# 4BitComputerSchematic.net
KiCad netlist of a schematic drawn in EasyEDA
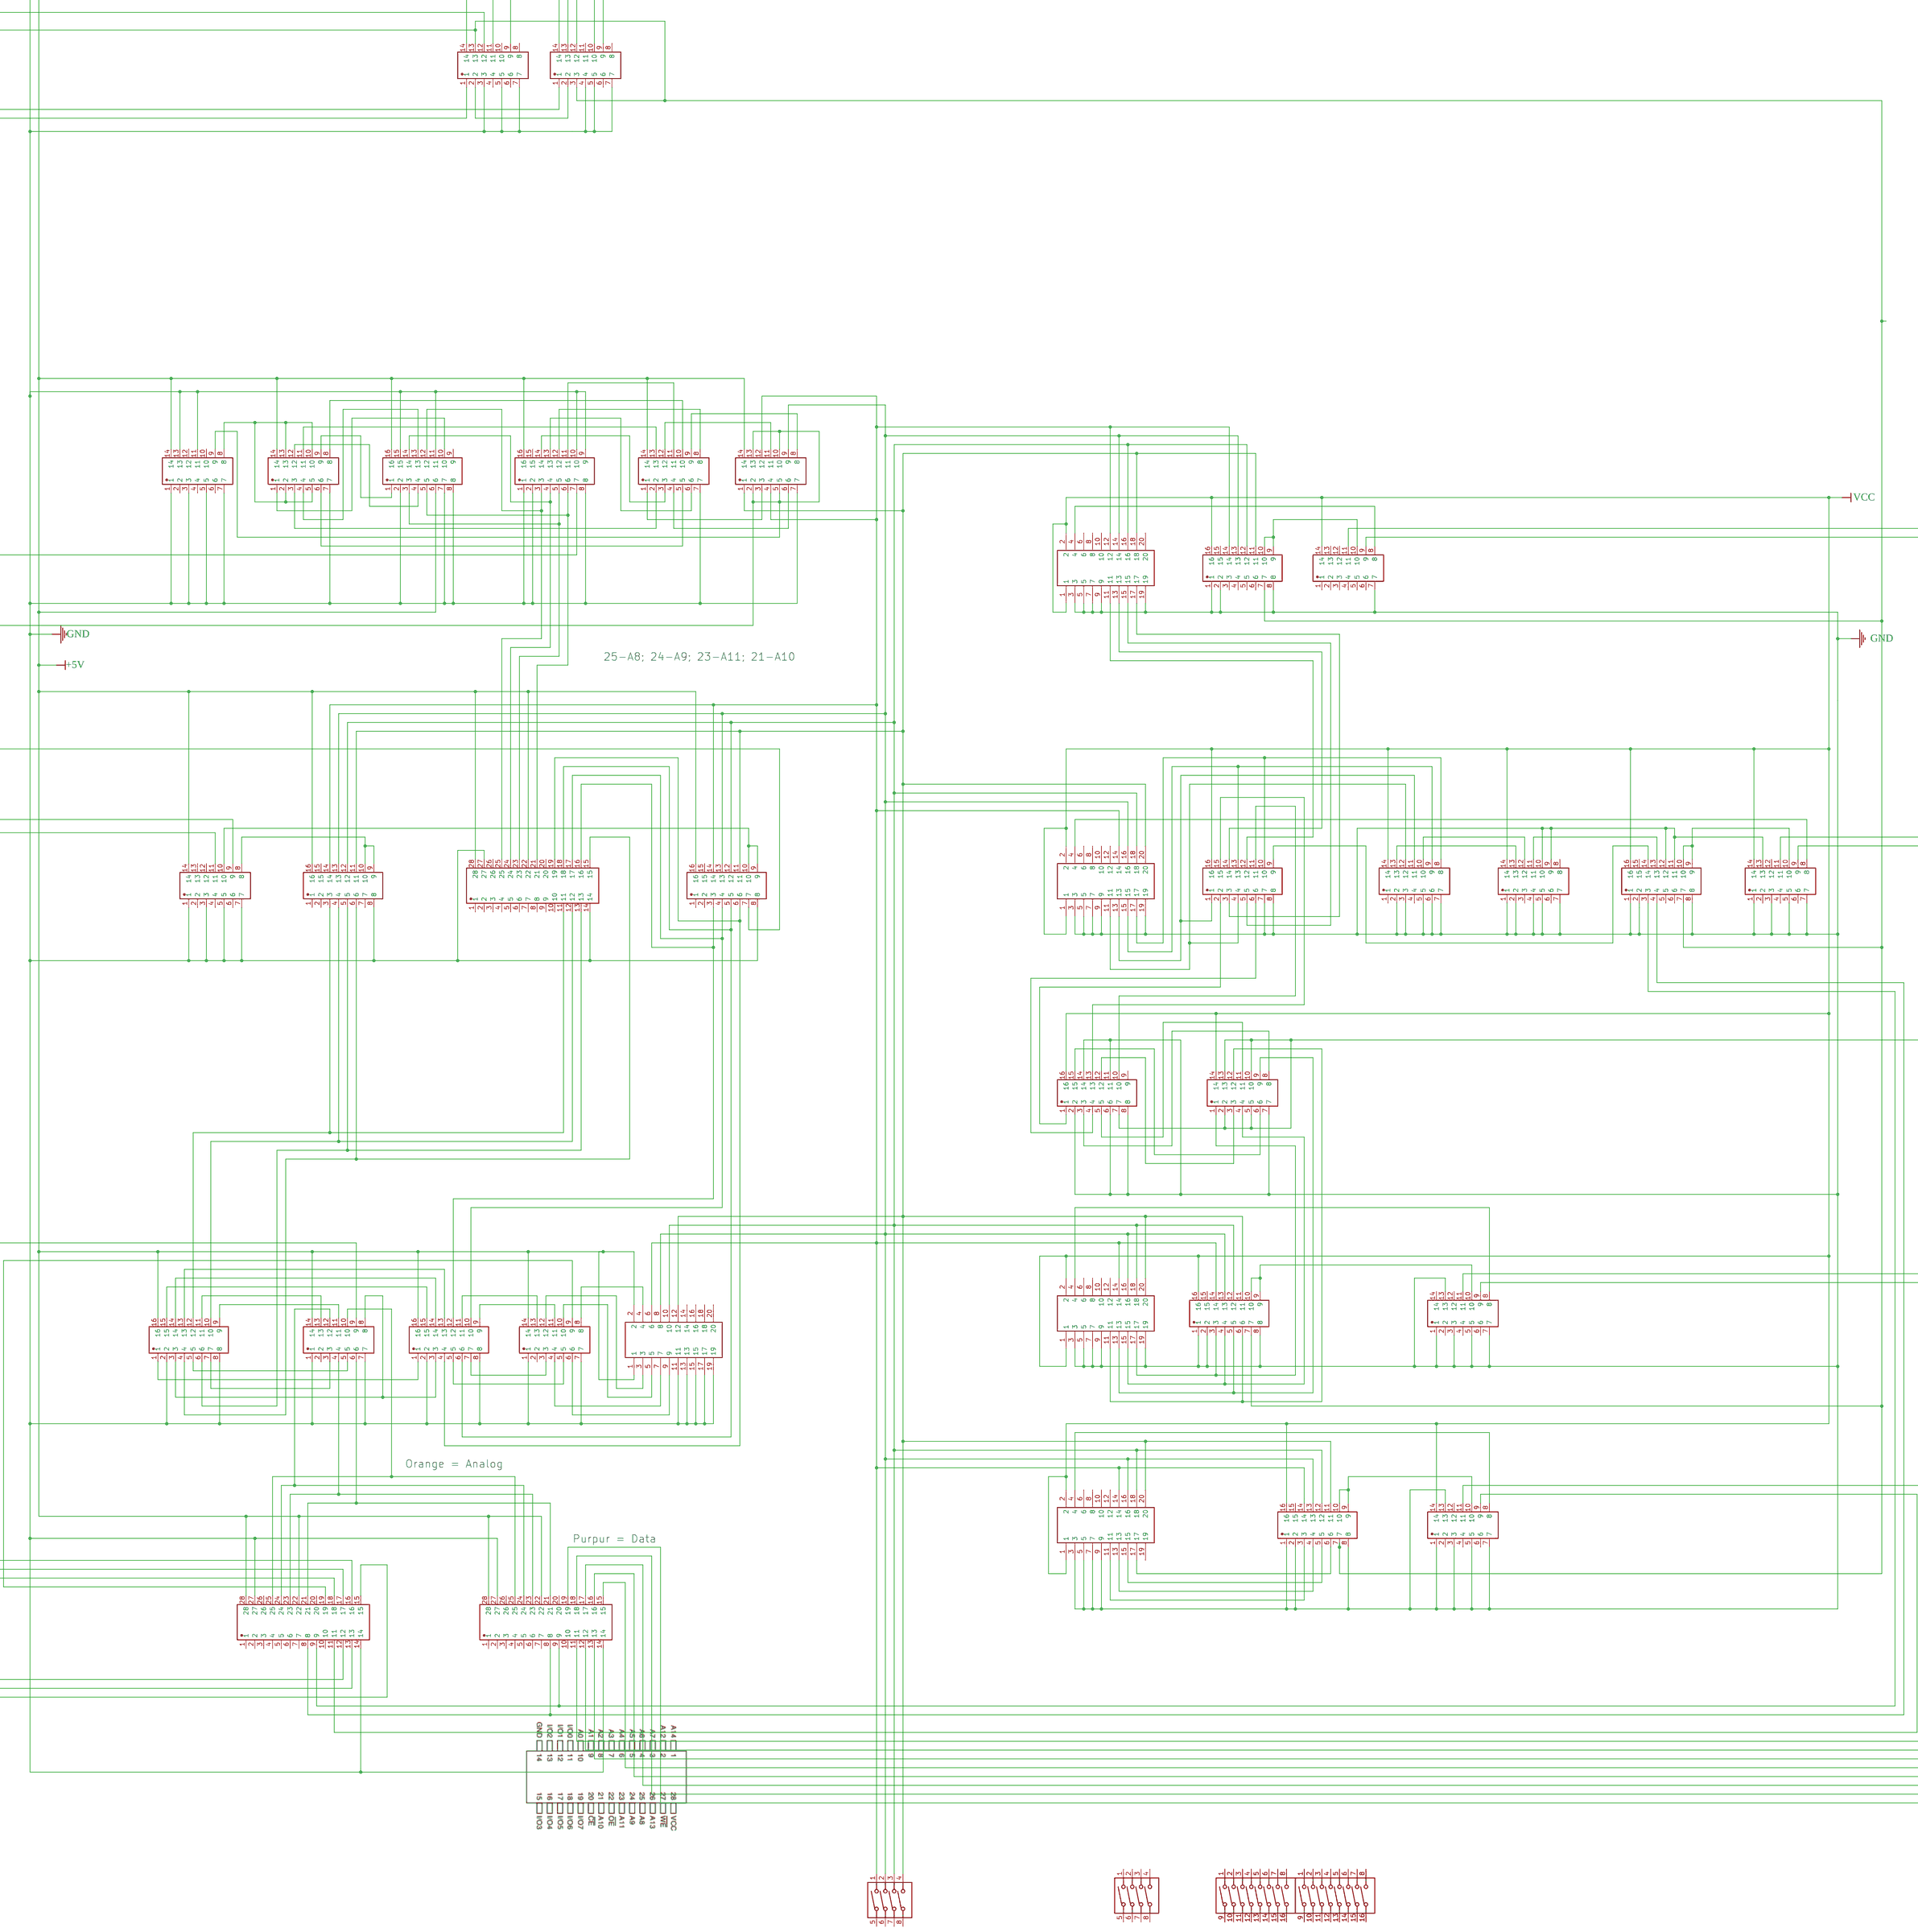
[diagram p0: schematic sheet]

(export (version "E")
  (design (tool "Eeschema 10.0.6"))
  (components
    (comp (ref "SK2")
      (value "IC seat 16P")
      (fields (field (name "Manufacturer Part") "IC-16P窄") (field (name "Manufacturer") "BOOMELE(博穆精密)"))
      (libsource (lib "") (part "IC seat 16P"))
    )
    (comp (ref "SK3")
      (value "ICS-20P")
      (fields (field (name "Manufacturer Part") "Z-ICS0S20P-NG00") (field (name "Manufacturer") "Ckmtw(灿科盟)"))
      (libsource (lib "") (part "ICS-20P"))
    )
    (comp (ref "SK4")
      (value "ICS-20P")
      (fields (field (name "Manufacturer Part") "Z-ICS0S20P-NG00") (field (name "Manufacturer") "Ckmtw(灿科盟)"))
      (libsource (lib "") (part "ICS-20P"))
    )
    (comp (ref "SK5")
      (value "ICS-20P")
      (fields (field (name "Manufacturer Part") "Z-ICS0S20P-NG00") (field (name "Manufacturer") "Ckmtw(灿科盟)"))
      (libsource (lib "") (part "ICS-20P"))
    )
    (comp (ref "SK7")
      (value "1-2199298-3")
      (fields (field (name "Manufacturer") "TE Connectivity(美国泰科)"))
      (libsource (lib "") (part "1-2199298-3"))
    )
    (comp (ref "SK8")
      (value "1-2199298-3")
      (fields (field (name "Manufacturer") "TE Connectivity(美国泰科)"))
      (libsource (lib "") (part "1-2199298-3"))
    )
    (comp (ref "SK9")
      (value "1-2199298-3")
      (fields (field (name "Manufacturer") "TE Connectivity(美国泰科)"))
      (libsource (lib "") (part "1-2199298-3"))
    )
    (comp (ref "SK10")
      (value "1-2199298-3")
      (fields (field (name "Manufacturer") "TE Connectivity(美国泰科)"))
      (libsource (lib "") (part "1-2199298-3"))
    )
    (comp (ref "SK11")
      (value "1-2199298-3")
      (fields (field (name "Manufacturer") "TE Connectivity(美国泰科)"))
      (libsource (lib "") (part "1-2199298-3"))
    )
    (comp (ref "SK12")
      (value "1-2199298-3")
      (fields (field (name "Manufacturer") "TE Connectivity(美国泰科)"))
      (libsource (lib "") (part "1-2199298-3"))
    )
    (comp (ref "SK13")
      (value "1-2199298-3")
      (fields (field (name "Manufacturer") "TE Connectivity(美国泰科)"))
      (libsource (lib "") (part "1-2199298-3"))
    )
    (comp (ref "SK14")
      (value "1-2199298-3")
      (fields (field (name "Manufacturer") "TE Connectivity(美国泰科)"))
      (libsource (lib "") (part "1-2199298-3"))
    )
    (comp (ref "SK15")
      (value "1-2199298-3")
      (fields (field (name "Manufacturer") "TE Connectivity(美国泰科)"))
      (libsource (lib "") (part "1-2199298-3"))
    )
    (comp (ref "SK16")
      (value "1-2199298-3")
      (fields (field (name "Manufacturer") "TE Connectivity(美国泰科)"))
      (libsource (lib "") (part "1-2199298-3"))
    )
    (comp (ref "SK21")
      (value "IC seat 16P")
      (fields (field (name "Manufacturer Part") "IC-16P窄") (field (name "Manufacturer") "BOOMELE(博穆精密)"))
      (libsource (lib "") (part "IC seat 16P"))
    )
    (comp (ref "SK22")
      (value "IC seat 16P")
      (fields (field (name "Manufacturer Part") "IC-16P窄") (field (name "Manufacturer") "BOOMELE(博穆精密)"))
      (libsource (lib "") (part "IC seat 16P"))
    )
    (comp (ref "SK23")
      (value "IC seat 16P")
      (fields (field (name "Manufacturer Part") "IC-16P窄") (field (name "Manufacturer") "BOOMELE(博穆精密)"))
      (libsource (lib "") (part "IC seat 16P"))
    )
    (comp (ref "SK26")
      (value "ICS-20P")
      (fields (field (name "Manufacturer Part") "Z-ICS0S20P-NG00") (field (name "Manufacturer") "Ckmtw(灿科盟)"))
      (libsource (lib "") (part "ICS-20P"))
    )
    (comp (ref "SK27")
      (value "IC seat 16P")
      (fields (field (name "Manufacturer Part") "IC-16P窄") (field (name "Manufacturer") "BOOMELE(博穆精密)"))
      (libsource (lib "") (part "IC seat 16P"))
    )
    (comp (ref "SK28")
      (value "IC seat 16P")
      (fields (field (name "Manufacturer Part") "IC-16P窄") (field (name "Manufacturer") "BOOMELE(博穆精密)"))
      (libsource (lib "") (part "IC seat 16P"))
    )
    (comp (ref "SK31")
      (value "1-2199298-3")
      (fields (field (name "Manufacturer") "TE Connectivity(美国泰科)"))
      (libsource (lib "") (part "1-2199298-3"))
    )
    (comp (ref "SK32")
      (value "1-2199298-3")
      (fields (field (name "Manufacturer") "TE Connectivity(美国泰科)"))
      (libsource (lib "") (part "1-2199298-3"))
    )
    (comp (ref "SK33")
      (value "1-2199298-3")
      (fields (field (name "Manufacturer") "TE Connectivity(美国泰科)"))
      (libsource (lib "") (part "1-2199298-3"))
    )
    (comp (ref "SK34")
      (value "1-2199298-3")
      (fields (field (name "Manufacturer") "TE Connectivity(美国泰科)"))
      (libsource (lib "") (part "1-2199298-3"))
    )
    (comp (ref "SK35")
      (value "1-2199298-3")
      (fields (field (name "Manufacturer") "TE Connectivity(美国泰科)"))
      (libsource (lib "") (part "1-2199298-3"))
    )
    (comp (ref "SK36")
      (value "1-2199298-3")
      (fields (field (name "Manufacturer") "TE Connectivity(美国泰科)"))
      (libsource (lib "") (part "1-2199298-3"))
    )
    (comp (ref "SK37")
      (value "ICS-20P")
      (fields (field (name "Manufacturer Part") "Z-ICS0S20P-NG00") (field (name "Manufacturer") "Ckmtw(灿科盟)"))
      (libsource (lib "") (part "ICS-20P"))
    )
    (comp (ref "SW1")
      (value "DSWB08LHGET")
      (fields (field (name "Manufacturer Part") "拨码开关,平拨开关,DSWB08LHGET") (field (name "Manufacturer") "YE"))
      (libsource (lib "") (part "DSWB08LHGET"))
    )
    (comp (ref "SW2")
      (value "DSWB08LHGET")
      (fields (field (name "Manufacturer Part") "拨码开关,平拨开关,DSWB08LHGET") (field (name "Manufacturer") "YE"))
      (libsource (lib "") (part "DSWB08LHGET"))
    )
    (comp (ref "SW3")
      (value "DSWB04LHGET")
      (fields (field (name "Manufacturer Part") "拨码开关,平拨开关,DSWB04LHGET") (field (name "Manufacturer") "YE"))
      (libsource (lib "") (part "DSWB04LHGET"))
    )
    (comp (ref "SW4")
      (value "DSWB04LHGET")
      (fields (field (name "Manufacturer Part") "拨码开关,平拨开关,DSWB04LHGET") (field (name "Manufacturer") "YE"))
      (libsource (lib "") (part "DSWB04LHGET"))
    )
    (comp (ref "U2")
      (value "X5621WV-2X14-C762D1196-1196")
      (fields
        (field (name "Manufacturer Part") "X5621WV-2x14-C762D1196-1196")
        (field (name "Manufacturer") "XKB Connectivity(中国星坤)")
      )
      (libsource (lib "") (part "X5621WV-2X14-C762D1196-1196"))
    )
    (comp (ref "U4")
      (value "X5621WV-2X14-C762D1196-1196")
      (fields
        (field (name "Manufacturer Part") "X5621WV-2x14-C762D1196-1196")
        (field (name "Manufacturer") "XKB Connectivity(中国星坤)")
      )
      (libsource (lib "") (part "X5621WV-2X14-C762D1196-1196"))
    )
    (comp (ref "U5")
      (value "IC-16P")
      (fields (field (name "Manufacturer") "ZHOURI(洲日)"))
      (libsource (lib "") (part "IC-16P"))
    )
    (comp (ref "U6")
      (value "IC-16P")
      (fields (field (name "Manufacturer") "ZHOURI(洲日)"))
      (libsource (lib "") (part "IC-16P"))
    )
    (comp (ref "U7")
      (value "IC-16P")
      (fields (field (name "Manufacturer") "ZHOURI(洲日)"))
      (libsource (lib "") (part "IC-16P"))
    )
    (comp (ref "U8")
      (value "IC-16P")
      (fields (field (name "Manufacturer") "ZHOURI(洲日)"))
      (libsource (lib "") (part "IC-16P"))
    )
    (comp (ref "U9")
      (value "IC-16P")
      (fields (field (name "Manufacturer") "ZHOURI(洲日)"))
      (libsource (lib "") (part "IC-16P"))
    )
    (comp (ref "U10")
      (value "IC-16P")
      (fields (field (name "Manufacturer") "ZHOURI(洲日)"))
      (libsource (lib "") (part "IC-16P"))
    )
    (comp (ref "U11")
      (value "X5621WV-2X14-C762D1196-1196")
      (fields
        (field (name "Manufacturer Part") "X5621WV-2x14-C762D1196-1196")
        (field (name "Manufacturer") "XKB Connectivity(中国星坤)")
      )
      (libsource (lib "") (part "X5621WV-2X14-C762D1196-1196"))
    )
  )
  (nets
    (net (code "1") (name "+5V") (class "Default")
      (node (ref "SK11") (pin "14") (pinfunction "14_14") (pintype "unspecified"))
      (node (ref "SK12") (pin "14") (pinfunction "14_14") (pintype "unspecified"))
      (node (ref "SK31") (pin "14") (pinfunction "14_14") (pintype "unspecified"))
      (node (ref "SK32") (pin "14") (pinfunction "14_14") (pintype "unspecified"))
      (node (ref "SK33") (pin "14") (pinfunction "14_14") (pintype "unspecified"))
      (node (ref "SK34") (pin "14") (pinfunction "14_14") (pintype "unspecified"))
      (node (ref "SK35") (pin "14") (pinfunction "14_14") (pintype "unspecified"))
      (node (ref "SK36") (pin "14") (pinfunction "14_14") (pintype "unspecified"))
      (node (ref "SK37") (pin "1") (pinfunction "1_1") (pintype "unspecified"))
      (node (ref "SK37") (pin "2") (pinfunction "2_2") (pintype "unspecified"))
      (node (ref "SK7") (pin "14") (pinfunction "14_14") (pintype "unspecified"))
      (node (ref "U10") (pin "16") (pinfunction "16_16") (pintype "unspecified"))
      (node (ref "U11") (pin "22") (pinfunction "22_22") (pintype "unspecified"))
      (node (ref "U11") (pin "28") (pinfunction "28_28") (pintype "unspecified"))
      (node (ref "U2") (pin "22") (pinfunction "22_22") (pintype "unspecified"))
      (node (ref "U2") (pin "28") (pinfunction "28_28") (pintype "unspecified"))
      (node (ref "U4") (pin "22") (pinfunction "22_22") (pintype "unspecified"))
      (node (ref "U4") (pin "28") (pinfunction "28_28") (pintype "unspecified"))
      (node (ref "U5") (pin "16") (pinfunction "16_16") (pintype "unspecified"))
      (node (ref "U5") (pin "6") (pinfunction "6_6") (pintype "unspecified"))
      (node (ref "U6") (pin "16") (pinfunction "16_16") (pintype "unspecified"))
      (node (ref "U7") (pin "16") (pinfunction "16_16") (pintype "unspecified"))
      (node (ref "U8") (pin "16") (pinfunction "16_16") (pintype "unspecified"))
      (node (ref "U9") (pin "16") (pinfunction "16_16") (pintype "unspecified"))
    )
    (net (code "2") (name "GND") (class "Default")
      (node (ref "SK10") (pin "7") (pinfunction "7_7") (pintype "unspecified"))
      (node (ref "SK11") (pin "11") (pinfunction "11_11") (pintype "unspecified"))
      (node (ref "SK11") (pin "3") (pinfunction "3_3") (pintype "unspecified"))
      (node (ref "SK11") (pin "5") (pinfunction "5_5") (pintype "unspecified"))
      (node (ref "SK11") (pin "7") (pinfunction "7_7") (pintype "unspecified"))
      (node (ref "SK11") (pin "9") (pinfunction "9_9") (pintype "unspecified"))
      (node (ref "SK12") (pin "1") (pinfunction "1_1") (pintype "unspecified"))
      (node (ref "SK12") (pin "3") (pinfunction "3_3") (pintype "unspecified"))
      (node (ref "SK12") (pin "5") (pinfunction "5_5") (pintype "unspecified"))
      (node (ref "SK12") (pin "7") (pinfunction "7_7") (pintype "unspecified"))
      (node (ref "SK13") (pin "1") (pinfunction "1_1") (pintype "unspecified"))
      (node (ref "SK13") (pin "13") (pinfunction "13_13") (pintype "unspecified"))
      (node (ref "SK13") (pin "3") (pinfunction "3_3") (pintype "unspecified"))
      (node (ref "SK13") (pin "5") (pinfunction "5_5") (pintype "unspecified"))
      (node (ref "SK13") (pin "7") (pinfunction "7_7") (pintype "unspecified"))
      (node (ref "SK14") (pin "1") (pinfunction "1_1") (pintype "unspecified"))
      (node (ref "SK14") (pin "13") (pinfunction "13_13") (pintype "unspecified"))
      (node (ref "SK14") (pin "3") (pinfunction "3_3") (pintype "unspecified"))
      (node (ref "SK14") (pin "5") (pinfunction "5_5") (pintype "unspecified"))
      (node (ref "SK14") (pin "7") (pinfunction "7_7") (pintype "unspecified"))
      (node (ref "SK15") (pin "7") (pinfunction "7_7") (pintype "unspecified"))
      (node (ref "SK16") (pin "1") (pinfunction "1_1") (pintype "unspecified"))
      (node (ref "SK16") (pin "10") (pinfunction "10_10") (pintype "unspecified"))
      (node (ref "SK16") (pin "2") (pinfunction "2_2") (pintype "unspecified"))
      (node (ref "SK16") (pin "4") (pinfunction "4_4") (pintype "unspecified"))
      (node (ref "SK16") (pin "5") (pinfunction "5_5") (pintype "unspecified"))
      (node (ref "SK16") (pin "7") (pinfunction "7_7") (pintype "unspecified"))
      (node (ref "SK16") (pin "9") (pinfunction "9_9") (pintype "unspecified"))
      (node (ref "SK2") (pin "1") (pinfunction "1_1") (pintype "unspecified"))
      (node (ref "SK2") (pin "2") (pinfunction "2_2") (pintype "unspecified"))
      (node (ref "SK2") (pin "8") (pinfunction "8_8") (pintype "unspecified"))
      (node (ref "SK21") (pin "7") (pinfunction "7_7") (pintype "unspecified"))
      (node (ref "SK21") (pin "8") (pinfunction "8_8") (pintype "unspecified"))
      (node (ref "SK22") (pin "1") (pinfunction "1_1") (pintype "unspecified"))
      (node (ref "SK22") (pin "2") (pinfunction "2_2") (pintype "unspecified"))
      (node (ref "SK22") (pin "8") (pinfunction "8_8") (pintype "unspecified"))
      (node (ref "SK23") (pin "1") (pinfunction "1_1") (pintype "unspecified"))
      (node (ref "SK23") (pin "11") (pinfunction "11_11") (pintype "unspecified"))
      (node (ref "SK23") (pin "12") (pinfunction "12_12") (pintype "unspecified"))
      (node (ref "SK23") (pin "2") (pinfunction "2_2") (pintype "unspecified"))
      (node (ref "SK23") (pin "8") (pinfunction "8_8") (pintype "unspecified"))
      (node (ref "SK26") (pin "3") (pinfunction "3_3") (pintype "unspecified"))
      (node (ref "SK26") (pin "5") (pinfunction "5_5") (pintype "unspecified"))
      (node (ref "SK26") (pin "7") (pinfunction "7_7") (pintype "unspecified"))
      (node (ref "SK26") (pin "9") (pinfunction "9_9") (pintype "unspecified"))
      (node (ref "SK27") (pin "1") (pinfunction "1_1") (pintype "unspecified"))
      (node (ref "SK27") (pin "2") (pinfunction "2_2") (pintype "unspecified"))
      (node (ref "SK27") (pin "8") (pinfunction "8_8") (pintype "unspecified"))
      (node (ref "SK28") (pin "11") (pinfunction "11_11") (pintype "unspecified"))
      (node (ref "SK28") (pin "14") (pinfunction "14_14") (pintype "unspecified"))
      (node (ref "SK28") (pin "2") (pinfunction "2_2") (pintype "unspecified"))
      (node (ref "SK28") (pin "6") (pinfunction "6_6") (pintype "unspecified"))
      (node (ref "SK28") (pin "8") (pinfunction "8_8") (pintype "unspecified"))
      (node (ref "SK3") (pin "19") (pinfunction "19_19") (pintype "unspecified"))
      (node (ref "SK3") (pin "3") (pinfunction "3_3") (pintype "unspecified"))
      (node (ref "SK3") (pin "5") (pinfunction "5_5") (pintype "unspecified"))
      (node (ref "SK3") (pin "7") (pinfunction "7_7") (pintype "unspecified"))
      (node (ref "SK3") (pin "9") (pinfunction "9_9") (pintype "unspecified"))
      (node (ref "SK31") (pin "1") (pinfunction "1_1") (pintype "unspecified"))
      (node (ref "SK31") (pin "7") (pinfunction "7_7") (pintype "unspecified"))
      (node (ref "SK32") (pin "1") (pinfunction "1_1") (pintype "unspecified"))
      (node (ref "SK32") (pin "7") (pinfunction "7_7") (pintype "unspecified"))
      (node (ref "SK33") (pin "1") (pinfunction "1_1") (pintype "unspecified"))
      (node (ref "SK33") (pin "11") (pinfunction "11_11") (pintype "unspecified"))
      (node (ref "SK33") (pin "13") (pinfunction "13_13") (pintype "unspecified"))
      (node (ref "SK33") (pin "3") (pinfunction "3_3") (pintype "unspecified"))
      (node (ref "SK33") (pin "5") (pinfunction "5_5") (pintype "unspecified"))
      (node (ref "SK33") (pin "7") (pinfunction "7_7") (pintype "unspecified"))
      (node (ref "SK34") (pin "7") (pinfunction "7_7") (pintype "unspecified"))
      (node (ref "SK35") (pin "7") (pinfunction "7_7") (pintype "unspecified"))
      (node (ref "SK36") (pin "7") (pinfunction "7_7") (pintype "unspecified"))
      (node (ref "SK37") (pin "11") (pinfunction "11_11") (pintype "unspecified"))
      (node (ref "SK37") (pin "13") (pinfunction "13_13") (pintype "unspecified"))
      (node (ref "SK37") (pin "15") (pinfunction "15_15") (pintype "unspecified"))
      (node (ref "SK37") (pin "17") (pinfunction "17_17") (pintype "unspecified"))
      (node (ref "SK37") (pin "19") (pinfunction "19_19") (pintype "unspecified"))
      (node (ref "SK4") (pin "19") (pinfunction "19_19") (pintype "unspecified"))
      (node (ref "SK4") (pin "3") (pinfunction "3_3") (pintype "unspecified"))
      (node (ref "SK4") (pin "5") (pinfunction "5_5") (pintype "unspecified"))
      (node (ref "SK4") (pin "7") (pinfunction "7_7") (pintype "unspecified"))
      (node (ref "SK4") (pin "9") (pinfunction "9_9") (pintype "unspecified"))
      (node (ref "SK5") (pin "19") (pinfunction "19_19") (pintype "unspecified"))
      (node (ref "SK5") (pin "3") (pinfunction "3_3") (pintype "unspecified"))
      (node (ref "SK5") (pin "5") (pinfunction "5_5") (pintype "unspecified"))
      (node (ref "SK5") (pin "7") (pinfunction "7_7") (pintype "unspecified"))
      (node (ref "SK5") (pin "9") (pinfunction "9_9") (pintype "unspecified"))
      (node (ref "SK7") (pin "10") (pinfunction "10_10") (pintype "unspecified"))
      (node (ref "SK7") (pin "12") (pinfunction "12_12") (pintype "unspecified"))
      (node (ref "SK7") (pin "13") (pinfunction "13_13") (pintype "unspecified"))
      (node (ref "SK7") (pin "4") (pinfunction "4_4") (pintype "unspecified"))
      (node (ref "SK7") (pin "5") (pinfunction "5_5") (pintype "unspecified"))
      (node (ref "SK7") (pin "7") (pinfunction "7_7") (pintype "unspecified"))
      (node (ref "SK7") (pin "9") (pinfunction "9_9") (pintype "unspecified"))
      (node (ref "SK8") (pin "2") (pinfunction "2_2") (pintype "unspecified"))
      (node (ref "SK8") (pin "3") (pinfunction "3_3") (pintype "unspecified"))
      (node (ref "SK8") (pin "5") (pinfunction "5_5") (pintype "unspecified"))
      (node (ref "SK8") (pin "6") (pinfunction "6_6") (pintype "unspecified"))
      (node (ref "SK8") (pin "7") (pinfunction "7_7") (pintype "unspecified"))
      (node (ref "SK9") (pin "1") (pinfunction "1_1") (pintype "unspecified"))
      (node (ref "SK9") (pin "13") (pinfunction "13_13") (pintype "unspecified"))
      (node (ref "SK9") (pin "3") (pinfunction "3_3") (pintype "unspecified"))
      (node (ref "SK9") (pin "5") (pinfunction "5_5") (pintype "unspecified"))
      (node (ref "SK9") (pin "7") (pinfunction "7_7") (pintype "unspecified"))
      (node (ref "U10") (pin "8") (pinfunction "8_8") (pintype "unspecified"))
      (node (ref "U11") (pin "14") (pinfunction "14_14") (pintype "unspecified"))
      (node (ref "U11") (pin "27") (pinfunction "27_27") (pintype "unspecified"))
      (node (ref "U2") (pin "14") (pinfunction "14_14") (pintype "unspecified"))
      (node (ref "U2") (pin "27") (pinfunction "27_27") (pintype "unspecified"))
      (node (ref "U4") (pin "14") (pinfunction "14_14") (pintype "unspecified"))
      (node (ref "U4") (pin "27") (pinfunction "27_27") (pintype "unspecified"))
      (node (ref "U5") (pin "11") (pinfunction "11_11") (pintype "unspecified"))
      (node (ref "U5") (pin "15") (pinfunction "15_15") (pintype "unspecified"))
      (node (ref "U5") (pin "2") (pinfunction "2_2") (pintype "unspecified"))
      (node (ref "U5") (pin "7") (pinfunction "7_7") (pintype "unspecified"))
      (node (ref "U5") (pin "8") (pinfunction "8_8") (pintype "unspecified"))
      (node (ref "U6") (pin "1") (pinfunction "1_1") (pintype "unspecified"))
      (node (ref "U6") (pin "10") (pinfunction "10_10") (pintype "unspecified"))
      (node (ref "U6") (pin "2") (pinfunction "2_2") (pintype "unspecified"))
      (node (ref "U6") (pin "8") (pinfunction "8_8") (pintype "unspecified"))
      (node (ref "U6") (pin "9") (pinfunction "9_9") (pintype "unspecified"))
      (node (ref "U7") (pin "8") (pinfunction "8_8") (pintype "unspecified"))
      (node (ref "U8") (pin "2") (pinfunction "2_2") (pintype "unspecified"))
      (node (ref "U8") (pin "8") (pinfunction "8_8") (pintype "unspecified"))
      (node (ref "U9") (pin "2") (pinfunction "2_2") (pintype "unspecified"))
      (node (ref "U9") (pin "8") (pinfunction "8_8") (pintype "unspecified"))
    )
    (net (code "3") (name "Net-(SK2-Pad3)") (class "Default")
      (node (ref "SK2") (pin "3") (pinfunction "3_3") (pintype "unspecified"))
      (node (ref "SK26") (pin "11") (pinfunction "11_11") (pintype "unspecified"))
    )
    (net (code "4") (name "Net-(SK2-Pad4)") (class "Default")
      (node (ref "SK2") (pin "4") (pinfunction "4_4") (pintype "unspecified"))
      (node (ref "SK26") (pin "13") (pinfunction "13_13") (pintype "unspecified"))
    )
    (net (code "5") (name "Net-(SK2-Pad5)") (class "Default")
      (node (ref "SK2") (pin "5") (pinfunction "5_5") (pintype "unspecified"))
      (node (ref "SK26") (pin "15") (pinfunction "15_15") (pintype "unspecified"))
    )
    (net (code "6") (name "Net-(SK2-Pad6)") (class "Default")
      (node (ref "SK2") (pin "6") (pinfunction "6_6") (pintype "unspecified"))
      (node (ref "SK26") (pin "17") (pinfunction "17_17") (pintype "unspecified"))
    )
    (net (code "7") (name "Net-(SK2-Pad11)") (class "Default")
      (node (ref "SK2") (pin "11") (pinfunction "11_11") (pintype "unspecified"))
      (node (ref "SK22") (pin "11") (pinfunction "11_11") (pintype "unspecified"))
      (node (ref "SK26") (pin "20") (pinfunction "20_20") (pintype "unspecified"))
      (node (ref "SK27") (pin "11") (pinfunction "11_11") (pintype "unspecified"))
      (node (ref "SK3") (pin "20") (pinfunction "20_20") (pintype "unspecified"))
      (node (ref "SK36") (pin "1") (pinfunction "1_1") (pintype "unspecified"))
      (node (ref "SK37") (pin "12") (pinfunction "12_12") (pintype "unspecified"))
      (node (ref "SK4") (pin "20") (pinfunction "20_20") (pintype "unspecified"))
      (node (ref "SK5") (pin "18") (pinfunction "18_18") (pintype "unspecified"))
      (node (ref "SW3") (pin "4") (pinfunction "4_4") (pintype "unspecified"))
      (node (ref "U10") (pin "11") (pinfunction "11_11") (pintype "unspecified"))
      (node (ref "U7") (pin "11") (pinfunction "11_11") (pintype "unspecified"))
    )
    (net (code "8") (name "Net-(SK2-Pad12)") (class "Default")
      (node (ref "SK2") (pin "12") (pinfunction "12_12") (pintype "unspecified"))
      (node (ref "SK22") (pin "12") (pinfunction "12_12") (pintype "unspecified"))
      (node (ref "SK26") (pin "18") (pinfunction "18_18") (pintype "unspecified"))
      (node (ref "SK27") (pin "12") (pinfunction "12_12") (pintype "unspecified"))
      (node (ref "SK3") (pin "18") (pinfunction "18_18") (pintype "unspecified"))
      (node (ref "SK37") (pin "10") (pinfunction "10_10") (pintype "unspecified"))
      (node (ref "SK4") (pin "18") (pinfunction "18_18") (pintype "unspecified"))
      (node (ref "SK5") (pin "16") (pinfunction "16_16") (pintype "unspecified"))
      (node (ref "SW3") (pin "3") (pinfunction "3_3") (pintype "unspecified"))
      (node (ref "U10") (pin "12") (pinfunction "12_12") (pintype "unspecified"))
      (node (ref "U7") (pin "12") (pinfunction "12_12") (pintype "unspecified"))
    )
    (net (code "9") (name "Net-(SK2-Pad13)") (class "Default")
      (node (ref "SK2") (pin "13") (pinfunction "13_13") (pintype "unspecified"))
      (node (ref "SK22") (pin "13") (pinfunction "13_13") (pintype "unspecified"))
      (node (ref "SK26") (pin "16") (pinfunction "16_16") (pintype "unspecified"))
      (node (ref "SK27") (pin "13") (pinfunction "13_13") (pintype "unspecified"))
      (node (ref "SK3") (pin "16") (pinfunction "16_16") (pintype "unspecified"))
      (node (ref "SK36") (pin "9") (pinfunction "9_9") (pintype "unspecified"))
      (node (ref "SK37") (pin "8") (pinfunction "8_8") (pintype "unspecified"))
      (node (ref "SK4") (pin "16") (pinfunction "16_16") (pintype "unspecified"))
      (node (ref "SK5") (pin "14") (pinfunction "14_14") (pintype "unspecified"))
      (node (ref "SW3") (pin "2") (pinfunction "2_2") (pintype "unspecified"))
      (node (ref "U10") (pin "13") (pinfunction "13_13") (pintype "unspecified"))
      (node (ref "U7") (pin "13") (pinfunction "13_13") (pintype "unspecified"))
    )
    (net (code "10") (name "Net-(SK2-Pad14)") (class "Default")
      (node (ref "SK2") (pin "14") (pinfunction "14_14") (pintype "unspecified"))
      (node (ref "SK22") (pin "14") (pinfunction "14_14") (pintype "unspecified"))
      (node (ref "SK26") (pin "14") (pinfunction "14_14") (pintype "unspecified"))
      (node (ref "SK27") (pin "14") (pinfunction "14_14") (pintype "unspecified"))
      (node (ref "SK3") (pin "14") (pinfunction "14_14") (pintype "unspecified"))
      (node (ref "SK36") (pin "12") (pinfunction "12_12") (pintype "unspecified"))
      (node (ref "SK36") (pin "4") (pinfunction "4_4") (pintype "unspecified"))
      (node (ref "SK37") (pin "6") (pinfunction "6_6") (pintype "unspecified"))
      (node (ref "SK4") (pin "14") (pinfunction "14_14") (pintype "unspecified"))
      (node (ref "SK5") (pin "12") (pinfunction "12_12") (pintype "unspecified"))
      (node (ref "SW3") (pin "1") (pinfunction "1_1") (pintype "unspecified"))
      (node (ref "U10") (pin "14") (pinfunction "14_14") (pintype "unspecified"))
      (node (ref "U7") (pin "14") (pinfunction "14_14") (pintype "unspecified"))
    )
    (net (code "11") (name "Net-(SK3-Pad4)") (class "Default")
      (node (ref "SK3") (pin "4") (pinfunction "4_4") (pintype "unspecified"))
      (node (ref "SK9") (pin "8") (pinfunction "8_8") (pintype "unspecified"))
    )
    (net (code "12") (name "Net-(SK7-Pad1)") (class "Default")
      (node (ref "SK7") (pin "1") (pinfunction "1_1") (pintype "unspecified"))
      (node (ref "U11") (pin "18") (pinfunction "18_18") (pintype "unspecified"))
    )
    (net (code "13") (name "Net-(SK9-Pad9)") (class "Default")
      (node (ref "SK9") (pin "9") (pinfunction "9_9") (pintype "unspecified"))
      (node (ref "U2") (pin "16") (pinfunction "16_16") (pintype "unspecified"))
    )
    (net (code "14") (name "Net-(SK9-Pad11)") (class "Default")
      (node (ref "SK9") (pin "11") (pinfunction "11_11") (pintype "unspecified"))
      (node (ref "U2") (pin "17") (pinfunction "17_17") (pintype "unspecified"))
    )
    (net (code "15") (name "Net-(SK10-Pad8)") (class "Default")
      (node (ref "SK10") (pin "8") (pinfunction "8_8") (pintype "unspecified"))
      (node (ref "SK5") (pin "4") (pinfunction "4_4") (pintype "unspecified"))
    )
    (net (code "16") (name "Net-(SK10-Pad9)") (class "Default")
      (node (ref "SK10") (pin "9") (pinfunction "9_9") (pintype "unspecified"))
      (node (ref "U2") (pin "18") (pinfunction "18_18") (pintype "unspecified"))
    )
    (net (code "17") (name "Net-(SK10-Pad10)") (class "Default")
      (node (ref "SK10") (pin "10") (pinfunction "10_10") (pintype "unspecified"))
      (node (ref "SK22") (pin "10") (pinfunction "10_10") (pintype "unspecified"))
      (node (ref "SK22") (pin "9") (pinfunction "9_9") (pintype "unspecified"))
    )
    (net (code "18") (name "Net-(SK10-Pad11)") (class "Default")
      (node (ref "SK10") (pin "11") (pinfunction "11_11") (pintype "unspecified"))
      (node (ref "U2") (pin "19") (pinfunction "19_19") (pintype "unspecified"))
    )
    (net (code "19") (name "Net-(SK11-Pad1)") (class "Default")
      (node (ref "SK11") (pin "1") (pinfunction "1_1") (pintype "unspecified"))
      (node (ref "U11") (pin "17") (pinfunction "17_17") (pintype "unspecified"))
    )
    (net (code "20") (name "Net-(SK11-Pad2)") (class "Default")
      (node (ref "SK11") (pin "2") (pinfunction "2_2") (pintype "unspecified"))
      (node (ref "SK7") (pin "2") (pinfunction "2_2") (pintype "unspecified"))
    )
    (net (code "21") (name "Net-(SK11-Pad12)") (class "Default")
      (node (ref "SK11") (pin "12") (pinfunction "12_12") (pintype "unspecified"))
      (node (ref "U6") (pin "7") (pinfunction "7_7") (pintype "unspecified"))
    )
    (net (code "22") (name "Net-(SK11-Pad13)") (class "Default")
      (node (ref "SK11") (pin "13") (pinfunction "13_13") (pintype "unspecified"))
      (node (ref "SK2") (pin "7") (pinfunction "7_7") (pintype "unspecified"))
      (node (ref "SK22") (pin "7") (pinfunction "7_7") (pintype "unspecified"))
      (node (ref "SK23") (pin "7") (pinfunction "7_7") (pintype "unspecified"))
      (node (ref "SK27") (pin "7") (pinfunction "7_7") (pintype "unspecified"))
      (node (ref "SK7") (pin "3") (pinfunction "3_3") (pintype "unspecified"))
      (node (ref "U10") (pin "7") (pinfunction "7_7") (pintype "unspecified"))
    )
    (net (code "23") (name "Net-(SK12-Pad8)") (class "Default")
      (node (ref "SK12") (pin "8") (pinfunction "8_8") (pintype "unspecified"))
      (node (ref "U7") (pin "10") (pinfunction "10_10") (pintype "unspecified"))
      (node (ref "U7") (pin "9") (pinfunction "9_9") (pintype "unspecified"))
    )
    (net (code "24") (name "Net-(SK12-Pad9)") (class "Default")
      (node (ref "SK12") (pin "9") (pinfunction "9_9") (pintype "unspecified"))
      (node (ref "U11") (pin "15") (pinfunction "15_15") (pintype "unspecified"))
    )
    (net (code "25") (name "Net-(SK12-Pad10)") (class "Default")
      (node (ref "SK12") (pin "10") (pinfunction "10_10") (pintype "unspecified"))
      (node (ref "U10") (pin "10") (pinfunction "10_10") (pintype "unspecified"))
      (node (ref "U10") (pin "9") (pinfunction "9_9") (pintype "unspecified"))
    )
    (net (code "26") (name "Net-(SK12-Pad11)") (class "Default")
      (node (ref "SK12") (pin "11") (pinfunction "11_11") (pintype "unspecified"))
      (node (ref "U11") (pin "13") (pinfunction "13_13") (pintype "unspecified"))
    )
    (net (code "27") (name "Net-(SK13-Pad8)") (class "Default")
      (node (ref "SK13") (pin "8") (pinfunction "8_8") (pintype "unspecified"))
      (node (ref "SK26") (pin "4") (pinfunction "4_4") (pintype "unspecified"))
    )
    (net (code "28") (name "Net-(SK13-Pad9)") (class "Default")
      (node (ref "SK13") (pin "9") (pinfunction "9_9") (pintype "unspecified"))
      (node (ref "U11") (pin "11") (pinfunction "11_11") (pintype "unspecified"))
    )
    (net (code "29") (name "Net-(SK13-Pad10)") (class "Default")
      (node (ref "SK13") (pin "10") (pinfunction "10_10") (pintype "unspecified"))
      (node (ref "SK2") (pin "10") (pinfunction "10_10") (pintype "unspecified"))
      (node (ref "SK2") (pin "9") (pinfunction "9_9") (pintype "unspecified"))
    )
    (net (code "30") (name "Net-(SK13-Pad11)") (class "Default")
      (node (ref "SK13") (pin "11") (pinfunction "11_11") (pintype "unspecified"))
      (node (ref "U2") (pin "11") (pinfunction "11_11") (pintype "unspecified"))
    )
    (net (code "31") (name "Net-(SK14-Pad8)") (class "Default")
      (node (ref "SK14") (pin "8") (pinfunction "8_8") (pintype "unspecified"))
      (node (ref "SK4") (pin "4") (pinfunction "4_4") (pintype "unspecified"))
    )
    (net (code "32") (name "Net-(SK14-Pad9)") (class "Default")
      (node (ref "SK14") (pin "9") (pinfunction "9_9") (pintype "unspecified"))
      (node (ref "U2") (pin "12") (pinfunction "12_12") (pintype "unspecified"))
    )
    (net (code "33") (name "Net-(SK14-Pad10)") (class "Default")
      (node (ref "SK14") (pin "10") (pinfunction "10_10") (pintype "unspecified"))
      (node (ref "SK27") (pin "10") (pinfunction "10_10") (pintype "unspecified"))
      (node (ref "SK27") (pin "9") (pinfunction "9_9") (pintype "unspecified"))
    )
    (net (code "34") (name "Net-(SK14-Pad11)") (class "Default")
      (node (ref "SK14") (pin "11") (pinfunction "11_11") (pintype "unspecified"))
      (node (ref "U2") (pin "13") (pinfunction "13_13") (pintype "unspecified"))
    )
    (net (code "35") (name "Net-(SK15-Pad1)") (class "Default")
      (node (ref "SK15") (pin "1") (pinfunction "1_1") (pintype "unspecified"))
      (node (ref "SK27") (pin "3") (pinfunction "3_3") (pintype "unspecified"))
      (node (ref "SK4") (pin "17") (pinfunction "17_17") (pintype "unspecified"))
    )
    (net (code "36") (name "Net-(SK15-Pad3)") (class "Default")
      (node (ref "SK15") (pin "3") (pinfunction "3_3") (pintype "unspecified"))
      (node (ref "SK28") (pin "12") (pinfunction "12_12") (pintype "unspecified"))
    )
    (net (code "37") (name "Net-(SK15-Pad4)") (class "Default")
      (node (ref "SK15") (pin "4") (pinfunction "4_4") (pintype "unspecified"))
      (node (ref "SK27") (pin "4") (pinfunction "4_4") (pintype "unspecified"))
      (node (ref "SK4") (pin "15") (pinfunction "15_15") (pintype "unspecified"))
    )
    (net (code "38") (name "Net-(SK15-Pad6)") (class "Default")
      (node (ref "SK15") (pin "6") (pinfunction "6_6") (pintype "unspecified"))
      (node (ref "SK28") (pin "15") (pinfunction "15_15") (pintype "unspecified"))
    )
    (net (code "39") (name "Net-(SK15-Pad8)") (class "Default")
      (node (ref "SK15") (pin "8") (pinfunction "8_8") (pintype "unspecified"))
      (node (ref "SK28") (pin "3") (pinfunction "3_3") (pintype "unspecified"))
    )
    (net (code "40") (name "Net-(SK15-Pad9)") (class "Default")
      (node (ref "SK15") (pin "9") (pinfunction "9_9") (pintype "unspecified"))
      (node (ref "SK27") (pin "5") (pinfunction "5_5") (pintype "unspecified"))
      (node (ref "SK4") (pin "13") (pinfunction "13_13") (pintype "unspecified"))
    )
    (net (code "41") (name "Net-(SK15-Pad10)") (class "Default")
      (node (ref "SK15") (pin "10") (pinfunction "10_10") (pintype "unspecified"))
      (node (ref "SK15") (pin "13") (pinfunction "13_13") (pintype "unspecified"))
      (node (ref "SK15") (pin "2") (pinfunction "2_2") (pintype "unspecified"))
      (node (ref "SK15") (pin "5") (pinfunction "5_5") (pintype "unspecified"))
      (node (ref "SK28") (pin "7") (pinfunction "7_7") (pintype "unspecified"))
      (node (ref "U2") (pin "15") (pinfunction "15_15") (pintype "unspecified"))
    )
    (net (code "42") (name "Net-(SK15-Pad11)") (class "Default")
      (node (ref "SK15") (pin "11") (pinfunction "11_11") (pintype "unspecified"))
      (node (ref "SK28") (pin "5") (pinfunction "5_5") (pintype "unspecified"))
    )
    (net (code "43") (name "Net-(SK15-Pad12)") (class "Default")
      (node (ref "SK15") (pin "12") (pinfunction "12_12") (pintype "unspecified"))
      (node (ref "SK27") (pin "6") (pinfunction "6_6") (pintype "unspecified"))
      (node (ref "SK4") (pin "11") (pinfunction "11_11") (pintype "unspecified"))
    )
    (net (code "44") (name "Net-(SK16-Pad11)") (class "Default")
      (node (ref "SK16") (pin "11") (pinfunction "11_11") (pintype "unspecified"))
      (node (ref "SK23") (pin "13") (pinfunction "13_13") (pintype "unspecified"))
    )
    (net (code "45") (name "Net-(SK16-Pad12)") (class "Default")
      (node (ref "SK16") (pin "12") (pinfunction "12_12") (pintype "unspecified"))
      (node (ref "SK8") (pin "10") (pinfunction "10_10") (pintype "unspecified"))
    )
    (net (code "46") (name "Net-(SK16-Pad13)") (class "Default")
      (node (ref "SK16") (pin "13") (pinfunction "13_13") (pintype "unspecified"))
      (node (ref "SK8") (pin "13") (pinfunction "13_13") (pintype "unspecified"))
    )
    (net (code "47") (name "Net-(SK21-Pad1)") (class "Default")
      (node (ref "SK21") (pin "1") (pinfunction "1_1") (pintype "unspecified"))
      (node (ref "SK3") (pin "13") (pinfunction "13_13") (pintype "unspecified"))
      (node (ref "SK8") (pin "11") (pinfunction "11_11") (pintype "unspecified"))
    )
    (net (code "48") (name "Net-(SK21-Pad2)") (class "Default")
      (node (ref "SK21") (pin "2") (pinfunction "2_2") (pintype "unspecified"))
      (node (ref "SK28") (pin "1") (pinfunction "1_1") (pintype "unspecified"))
    )
    (net (code "49") (name "Net-(SK21-Pad3)") (class "Default")
      (node (ref "SK21") (pin "3") (pinfunction "3_3") (pintype "unspecified"))
      (node (ref "SK5") (pin "17") (pinfunction "17_17") (pintype "unspecified"))
    )
    (net (code "50") (name "Net-(SK21-Pad4)") (class "Default")
      (node (ref "SK21") (pin "4") (pinfunction "4_4") (pintype "unspecified"))
      (node (ref "SK3") (pin "11") (pinfunction "11_11") (pintype "unspecified"))
      (node (ref "SK8") (pin "12") (pinfunction "12_12") (pintype "unspecified"))
    )
    (net (code "51") (name "Net-(SK21-Pad5)") (class "Default")
      (node (ref "SK21") (pin "5") (pinfunction "5_5") (pintype "unspecified"))
      (node (ref "SK5") (pin "15") (pinfunction "15_15") (pintype "unspecified"))
    )
    (net (code "52") (name "Net-(SK21-Pad6)") (class "Default")
      (node (ref "SK21") (pin "6") (pinfunction "6_6") (pintype "unspecified"))
      (node (ref "SK28") (pin "4") (pinfunction "4_4") (pintype "unspecified"))
    )
    (net (code "53") (name "Net-(SK21-Pad9)") (class "Default")
      (node (ref "SK21") (pin "9") (pinfunction "9_9") (pintype "unspecified"))
      (node (ref "SK23") (pin "14") (pinfunction "14_14") (pintype "unspecified"))
    )
    (net (code "54") (name "Net-(SK21-Pad10)") (class "Default")
      (node (ref "SK21") (pin "10") (pinfunction "10_10") (pintype "unspecified"))
      (node (ref "SK3") (pin "17") (pinfunction "17_17") (pintype "unspecified"))
      (node (ref "SK8") (pin "8") (pinfunction "8_8") (pintype "unspecified"))
    )
    (net (code "55") (name "Net-(SK21-Pad11)") (class "Default")
      (node (ref "SK21") (pin "11") (pinfunction "11_11") (pintype "unspecified"))
      (node (ref "SK28") (pin "10") (pinfunction "10_10") (pintype "unspecified"))
    )
    (net (code "56") (name "Net-(SK21-Pad12)") (class "Default")
      (node (ref "SK21") (pin "12") (pinfunction "12_12") (pintype "unspecified"))
      (node (ref "SK5") (pin "11") (pinfunction "11_11") (pintype "unspecified"))
    )
    (net (code "57") (name "Net-(SK21-Pad13)") (class "Default")
      (node (ref "SK21") (pin "13") (pinfunction "13_13") (pintype "unspecified"))
      (node (ref "SK3") (pin "15") (pinfunction "15_15") (pintype "unspecified"))
      (node (ref "SK8") (pin "9") (pinfunction "9_9") (pintype "unspecified"))
    )
    (net (code "58") (name "Net-(SK21-Pad14)") (class "Default")
      (node (ref "SK21") (pin "14") (pinfunction "14_14") (pintype "unspecified"))
      (node (ref "SK5") (pin "13") (pinfunction "13_13") (pintype "unspecified"))
    )
    (net (code "59") (name "Net-(SK21-Pad15)") (class "Default")
      (node (ref "SK21") (pin "15") (pinfunction "15_15") (pintype "unspecified"))
      (node (ref "SK28") (pin "13") (pinfunction "13_13") (pintype "unspecified"))
    )
    (net (code "60") (name "Net-(SK23-Pad3)") (class "Default")
      (node (ref "SK23") (pin "3") (pinfunction "3_3") (pintype "unspecified"))
      (node (ref "U11") (pin "9") (pinfunction "9_9") (pintype "unspecified"))
      (node (ref "U2") (pin "9") (pinfunction "9_9") (pintype "unspecified"))
    )
    (net (code "61") (name "Net-(SK23-Pad4)") (class "Default")
      (node (ref "SK23") (pin "4") (pinfunction "4_4") (pintype "unspecified"))
      (node (ref "U11") (pin "8") (pinfunction "8_8") (pintype "unspecified"))
      (node (ref "U2") (pin "8") (pinfunction "8_8") (pintype "unspecified"))
    )
    (net (code "62") (name "Net-(SK23-Pad10)") (class "Default")
      (node (ref "SK23") (pin "10") (pinfunction "10_10") (pintype "unspecified"))
      (node (ref "SK23") (pin "9") (pinfunction "9_9") (pintype "unspecified"))
      (node (ref "SK9") (pin "10") (pinfunction "10_10") (pintype "unspecified"))
    )
    (net (code "63") (name "Net-(SK31-Pad3)") (class "Default")
      (node (ref "SK31") (pin "3") (pinfunction "3_3") (pintype "unspecified"))
      (node (ref "U9") (pin "7") (pinfunction "7_7") (pintype "unspecified"))
    )
    (net (code "64") (name "Net-(SK31-Pad4)") (class "Default")
      (node (ref "SK31") (pin "4") (pinfunction "4_4") (pintype "unspecified"))
      (node (ref "SK37") (pin "7") (pinfunction "7_7") (pintype "unspecified"))
    )
    (net (code "65") (name "Net-(SK31-Pad5)") (class "Default")
      (node (ref "SK31") (pin "5") (pinfunction "5_5") (pintype "unspecified"))
      (node (ref "U9") (pin "5") (pinfunction "5_5") (pintype "unspecified"))
    )
    (net (code "66") (name "Net-(SK31-Pad6)") (class "Default")
      (node (ref "SK31") (pin "6") (pinfunction "6_6") (pintype "unspecified"))
      (node (ref "SK37") (pin "9") (pinfunction "9_9") (pintype "unspecified"))
    )
    (net (code "67") (name "Net-(SK31-Pad8)") (class "Default")
      (node (ref "SK31") (pin "8") (pinfunction "8_8") (pintype "unspecified"))
      (node (ref "SK37") (pin "4") (pinfunction "4_4") (pintype "unspecified"))
    )
    (net (code "68") (name "Net-(SK31-Pad9)") (class "Default")
      (node (ref "SK31") (pin "9") (pinfunction "9_9") (pintype "unspecified"))
      (node (ref "U11") (pin "19") (pinfunction "19_19") (pintype "unspecified"))
    )
    (net (code "69") (name "Net-(SK31-Pad10)") (class "Default")
      (node (ref "SK31") (pin "10") (pinfunction "10_10") (pintype "unspecified"))
      (node (ref "SK37") (pin "5") (pinfunction "5_5") (pintype "unspecified"))
    )
    (net (code "70") (name "Net-(SK31-Pad11)") (class "Default")
      (node (ref "SK31") (pin "11") (pinfunction "11_11") (pintype "unspecified"))
      (node (ref "U9") (pin "9") (pinfunction "9_9") (pintype "unspecified"))
    )
    (net (code "71") (name "Net-(SK31-Pad12)") (class "Default")
      (node (ref "SK31") (pin "12") (pinfunction "12_12") (pintype "unspecified"))
      (node (ref "SK37") (pin "3") (pinfunction "3_3") (pintype "unspecified"))
    )
    (net (code "72") (name "Net-(SK31-Pad13)") (class "Default")
      (node (ref "SK31") (pin "13") (pinfunction "13_13") (pintype "unspecified"))
      (node (ref "U9") (pin "11") (pinfunction "11_11") (pintype "unspecified"))
    )
    (net (code "73") (name "Net-(SK32-Pad3)") (class "Default")
      (node (ref "SK32") (pin "3") (pinfunction "3_3") (pintype "unspecified"))
      (node (ref "U8") (pin "7") (pinfunction "7_7") (pintype "unspecified"))
    )
    (net (code "74") (name "Net-(SK32-Pad4)") (class "Default")
      (node (ref "SK32") (pin "4") (pinfunction "4_4") (pintype "unspecified"))
      (node (ref "U11") (pin "23") (pinfunction "23_23") (pintype "unspecified"))
      (node (ref "U2") (pin "23") (pinfunction "23_23") (pintype "unspecified"))
    )
    (net (code "75") (name "Net-(SK32-Pad5)") (class "Default")
      (node (ref "SK32") (pin "5") (pinfunction "5_5") (pintype "unspecified"))
      (node (ref "U8") (pin "5") (pinfunction "5_5") (pintype "unspecified"))
    )
    (net (code "76") (name "Net-(SK32-Pad6)") (class "Default")
      (node (ref "SK32") (pin "6") (pinfunction "6_6") (pintype "unspecified"))
      (node (ref "U11") (pin "21") (pinfunction "21_21") (pintype "unspecified"))
      (node (ref "U2") (pin "21") (pinfunction "21_21") (pintype "unspecified"))
    )
    (net (code "77") (name "Net-(SK32-Pad8)") (class "Default")
      (node (ref "SK32") (pin "8") (pinfunction "8_8") (pintype "unspecified"))
      (node (ref "U8") (pin "3") (pinfunction "3_3") (pintype "unspecified"))
      (node (ref "U9") (pin "3") (pinfunction "3_3") (pintype "unspecified"))
    )
    (net (code "78") (name "Net-(SK32-Pad9)") (class "Default")
      (node (ref "SK32") (pin "9") (pinfunction "9_9") (pintype "unspecified"))
      (node (ref "U11") (pin "12") (pinfunction "12_12") (pintype "unspecified"))
    )
    (net (code "79") (name "Net-(SK32-Pad10)") (class "Default")
      (node (ref "SK32") (pin "10") (pinfunction "10_10") (pintype "unspecified"))
      (node (ref "U11") (pin "25") (pinfunction "25_25") (pintype "unspecified"))
      (node (ref "U2") (pin "25") (pinfunction "25_25") (pintype "unspecified"))
    )
    (net (code "80") (name "Net-(SK32-Pad11)") (class "Default")
      (node (ref "SK32") (pin "11") (pinfunction "11_11") (pintype "unspecified"))
      (node (ref "U8") (pin "9") (pinfunction "9_9") (pintype "unspecified"))
    )
    (net (code "81") (name "Net-(SK32-Pad12)") (class "Default")
      (node (ref "SK32") (pin "12") (pinfunction "12_12") (pintype "unspecified"))
      (node (ref "U11") (pin "24") (pinfunction "24_24") (pintype "unspecified"))
      (node (ref "U2") (pin "24") (pinfunction "24_24") (pintype "unspecified"))
    )
    (net (code "82") (name "Net-(SK32-Pad13)") (class "Default")
      (node (ref "SK32") (pin "13") (pinfunction "13_13") (pintype "unspecified"))
      (node (ref "U8") (pin "11") (pinfunction "11_11") (pintype "unspecified"))
    )
    (net (code "83") (name "Net-(SK33-Pad8)") (class "Default")
      (node (ref "SK33") (pin "8") (pinfunction "8_8") (pintype "unspecified"))
      (node (ref "SK34") (pin "10") (pinfunction "10_10") (pintype "unspecified"))
      (node (ref "SK34") (pin "13") (pinfunction "13_13") (pintype "unspecified"))
      (node (ref "SK34") (pin "2") (pinfunction "2_2") (pintype "unspecified"))
      (node (ref "SK34") (pin "5") (pinfunction "5_5") (pintype "unspecified"))
    )
    (net (code "84") (name "Net-(SK33-Pad9)") (class "Default")
      (node (ref "SK33") (pin "9") (pinfunction "9_9") (pintype "unspecified"))
      (node (ref "SK36") (pin "10") (pinfunction "10_10") (pintype "unspecified"))
      (node (ref "SK36") (pin "13") (pinfunction "13_13") (pintype "unspecified"))
      (node (ref "SK36") (pin "2") (pinfunction "2_2") (pintype "unspecified"))
      (node (ref "SK36") (pin "5") (pinfunction "5_5") (pintype "unspecified"))
      (node (ref "U11") (pin "16") (pinfunction "16_16") (pintype "unspecified"))
    )
    (net (code "85") (name "Net-(SK34-Pad1)") (class "Default")
      (node (ref "SK34") (pin "1") (pinfunction "1_1") (pintype "unspecified"))
      (node (ref "U5") (pin "10") (pinfunction "10_10") (pintype "unspecified"))
    )
    (net (code "86") (name "Net-(SK34-Pad3)") (class "Default")
      (node (ref "SK34") (pin "3") (pinfunction "3_3") (pintype "unspecified"))
      (node (ref "SK35") (pin "2") (pinfunction "2_2") (pintype "unspecified"))
    )
    (net (code "87") (name "Net-(SK34-Pad4)") (class "Default")
      (node (ref "SK34") (pin "4") (pinfunction "4_4") (pintype "unspecified"))
      (node (ref "U5") (pin "13") (pinfunction "13_13") (pintype "unspecified"))
    )
    (net (code "88") (name "Net-(SK34-Pad6)") (class "Default")
      (node (ref "SK34") (pin "6") (pinfunction "6_6") (pintype "unspecified"))
      (node (ref "SK35") (pin "5") (pinfunction "5_5") (pintype "unspecified"))
    )
    (net (code "89") (name "Net-(SK34-Pad8)") (class "Default")
      (node (ref "SK34") (pin "8") (pinfunction "8_8") (pintype "unspecified"))
      (node (ref "SK35") (pin "10") (pinfunction "10_10") (pintype "unspecified"))
    )
    (net (code "90") (name "Net-(SK34-Pad9)") (class "Default")
      (node (ref "SK34") (pin "9") (pinfunction "9_9") (pintype "unspecified"))
      (node (ref "U5") (pin "1") (pinfunction "1_1") (pintype "unspecified"))
    )
    (net (code "91") (name "Net-(SK34-Pad11)") (class "Default")
      (node (ref "SK34") (pin "11") (pinfunction "11_11") (pintype "unspecified"))
      (node (ref "SK35") (pin "13") (pinfunction "13_13") (pintype "unspecified"))
    )
    (net (code "92") (name "Net-(SK34-Pad12)") (class "Default")
      (node (ref "SK34") (pin "12") (pinfunction "12_12") (pintype "unspecified"))
      (node (ref "U5") (pin "4") (pinfunction "4_4") (pintype "unspecified"))
    )
    (net (code "93") (name "Net-(SK35-Pad1)") (class "Default")
      (node (ref "SK35") (pin "1") (pinfunction "1_1") (pintype "unspecified"))
      (node (ref "SK36") (pin "3") (pinfunction "3_3") (pintype "unspecified"))
    )
    (net (code "94") (name "Net-(SK35-Pad3)") (class "Default")
      (node (ref "SK35") (pin "3") (pinfunction "3_3") (pintype "unspecified"))
      (node (ref "U6") (pin "14") (pinfunction "14_14") (pintype "unspecified"))
    )
    (net (code "95") (name "Net-(SK35-Pad4)") (class "Default")
      (node (ref "SK35") (pin "4") (pinfunction "4_4") (pintype "unspecified"))
      (node (ref "SK36") (pin "6") (pinfunction "6_6") (pintype "unspecified"))
    )
    (net (code "96") (name "Net-(SK35-Pad6)") (class "Default")
      (node (ref "SK35") (pin "6") (pinfunction "6_6") (pintype "unspecified"))
      (node (ref "U6") (pin "13") (pinfunction "13_13") (pintype "unspecified"))
    )
    (net (code "97") (name "Net-(SK35-Pad8)") (class "Default")
      (node (ref "SK35") (pin "8") (pinfunction "8_8") (pintype "unspecified"))
      (node (ref "U6") (pin "12") (pinfunction "12_12") (pintype "unspecified"))
    )
    (net (code "98") (name "Net-(SK35-Pad9)") (class "Default")
      (node (ref "SK35") (pin "9") (pinfunction "9_9") (pintype "unspecified"))
      (node (ref "SK36") (pin "8") (pinfunction "8_8") (pintype "unspecified"))
    )
    (net (code "99") (name "Net-(SK35-Pad11)") (class "Default")
      (node (ref "SK35") (pin "11") (pinfunction "11_11") (pintype "unspecified"))
      (node (ref "U6") (pin "11") (pinfunction "11_11") (pintype "unspecified"))
    )
    (net (code "100") (name "Net-(SK35-Pad12)") (class "Default")
      (node (ref "SK35") (pin "12") (pinfunction "12_12") (pintype "unspecified"))
      (node (ref "SK36") (pin "11") (pinfunction "11_11") (pintype "unspecified"))
    )
    (net (code "101") (name "Net-(U4-Pad11)") (class "Default")
      (node (ref "U4") (pin "11") (pinfunction "11_11") (pintype "unspecified"))
      (node (ref "U7") (pin "3") (pinfunction "3_3") (pintype "unspecified"))
      (node (ref "U8") (pin "12") (pinfunction "12_12") (pintype "unspecified"))
    )
    (net (code "102") (name "Net-(U4-Pad12)") (class "Default")
      (node (ref "U4") (pin "12") (pinfunction "12_12") (pintype "unspecified"))
      (node (ref "U7") (pin "4") (pinfunction "4_4") (pintype "unspecified"))
      (node (ref "U8") (pin "10") (pinfunction "10_10") (pintype "unspecified"))
    )
    (net (code "103") (name "Net-(U4-Pad13)") (class "Default")
      (node (ref "U4") (pin "13") (pinfunction "13_13") (pintype "unspecified"))
      (node (ref "U7") (pin "5") (pinfunction "5_5") (pintype "unspecified"))
      (node (ref "U8") (pin "6") (pinfunction "6_6") (pintype "unspecified"))
    )
    (net (code "104") (name "Net-(U4-Pad15)") (class "Default")
      (node (ref "U4") (pin "15") (pinfunction "15_15") (pintype "unspecified"))
      (node (ref "U7") (pin "6") (pinfunction "6_6") (pintype "unspecified"))
      (node (ref "U8") (pin "4") (pinfunction "4_4") (pintype "unspecified"))
    )
    (net (code "105") (name "Net-(U4-Pad21)") (class "Default")
      (node (ref "U4") (pin "21") (pinfunction "21_21") (pintype "unspecified"))
      (node (ref "U5") (pin "5") (pinfunction "5_5") (pintype "unspecified"))
      (node (ref "U6") (pin "6") (pinfunction "6_6") (pintype "unspecified"))
    )
    (net (code "106") (name "Net-(U4-Pad23)") (class "Default")
      (node (ref "U4") (pin "23") (pinfunction "23_23") (pintype "unspecified"))
      (node (ref "U5") (pin "3") (pinfunction "3_3") (pintype "unspecified"))
      (node (ref "U6") (pin "5") (pinfunction "5_5") (pintype "unspecified"))
    )
    (net (code "107") (name "Net-(U4-Pad24)") (class "Default")
      (node (ref "U4") (pin "24") (pinfunction "24_24") (pintype "unspecified"))
      (node (ref "U5") (pin "14") (pinfunction "14_14") (pintype "unspecified"))
      (node (ref "U6") (pin "4") (pinfunction "4_4") (pintype "unspecified"))
    )
    (net (code "108") (name "Net-(U4-Pad25)") (class "Default")
      (node (ref "U4") (pin "25") (pinfunction "25_25") (pintype "unspecified"))
      (node (ref "U5") (pin "12") (pinfunction "12_12") (pintype "unspecified"))
      (node (ref "U6") (pin "3") (pinfunction "3_3") (pintype "unspecified"))
    )
    (net (code "109") (name "Net-(U8-Pad1)") (class "Default")
      (node (ref "U8") (pin "1") (pinfunction "1_1") (pintype "unspecified"))
      (node (ref "U9") (pin "1") (pinfunction "1_1") (pintype "unspecified"))
    )
    (net (code "110") (name "Net-(U8-Pad13)") (class "Default")
      (node (ref "U8") (pin "13") (pinfunction "13_13") (pintype "unspecified"))
      (node (ref "U9") (pin "13") (pinfunction "13_13") (pintype "unspecified"))
    )
    (net (code "111") (name "Net-(U8-Pad14)") (class "Default")
      (node (ref "U8") (pin "14") (pinfunction "14_14") (pintype "unspecified"))
      (node (ref "U9") (pin "14") (pinfunction "14_14") (pintype "unspecified"))
    )
    (net (code "112") (name "Net-(U8-Pad15)") (class "Default")
      (node (ref "U8") (pin "15") (pinfunction "15_15") (pintype "unspecified"))
      (node (ref "U9") (pin "15") (pinfunction "15_15") (pintype "unspecified"))
    )
    (net (code "113") (name "Net-(U10-Pad3)") (class "Default")
      (node (ref "U10") (pin "3") (pinfunction "3_3") (pintype "unspecified"))
      (node (ref "U4") (pin "16") (pinfunction "16_16") (pintype "unspecified"))
      (node (ref "U9") (pin "12") (pinfunction "12_12") (pintype "unspecified"))
    )
    (net (code "114") (name "Net-(U10-Pad4)") (class "Default")
      (node (ref "U10") (pin "4") (pinfunction "4_4") (pintype "unspecified"))
      (node (ref "U4") (pin "17") (pinfunction "17_17") (pintype "unspecified"))
      (node (ref "U9") (pin "10") (pinfunction "10_10") (pintype "unspecified"))
    )
    (net (code "115") (name "Net-(U10-Pad5)") (class "Default")
      (node (ref "U10") (pin "5") (pinfunction "5_5") (pintype "unspecified"))
      (node (ref "U4") (pin "18") (pinfunction "18_18") (pintype "unspecified"))
      (node (ref "U9") (pin "6") (pinfunction "6_6") (pintype "unspecified"))
    )
    (net (code "116") (name "Net-(U10-Pad6)") (class "Default")
      (node (ref "U10") (pin "6") (pinfunction "6_6") (pintype "unspecified"))
      (node (ref "U4") (pin "19") (pinfunction "19_19") (pintype "unspecified"))
      (node (ref "U9") (pin "4") (pinfunction "4_4") (pintype "unspecified"))
    )
    (net (code "117") (name "VCC") (class "Default")
      (node (ref "SK10") (pin "14") (pinfunction "14_14") (pintype "unspecified"))
      (node (ref "SK13") (pin "14") (pinfunction "14_14") (pintype "unspecified"))
      (node (ref "SK15") (pin "14") (pinfunction "14_14") (pintype "unspecified"))
      (node (ref "SK16") (pin "14") (pinfunction "14_14") (pintype "unspecified"))
      (node (ref "SK2") (pin "16") (pinfunction "16_16") (pintype "unspecified"))
      (node (ref "SK21") (pin "16") (pinfunction "16_16") (pintype "unspecified"))
      (node (ref "SK22") (pin "16") (pinfunction "16_16") (pintype "unspecified"))
      (node (ref "SK23") (pin "16") (pinfunction "16_16") (pintype "unspecified"))
      (node (ref "SK26") (pin "1") (pinfunction "1_1") (pintype "unspecified"))
      (node (ref "SK26") (pin "2") (pinfunction "2_2") (pintype "unspecified"))
      (node (ref "SK27") (pin "16") (pinfunction "16_16") (pintype "unspecified"))
      (node (ref "SK28") (pin "16") (pinfunction "16_16") (pintype "unspecified"))
      (node (ref "SK3") (pin "1") (pinfunction "1_1") (pintype "unspecified"))
      (node (ref "SK3") (pin "2") (pinfunction "2_2") (pintype "unspecified"))
      (node (ref "SK4") (pin "1") (pinfunction "1_1") (pintype "unspecified"))
      (node (ref "SK4") (pin "2") (pinfunction "2_2") (pintype "unspecified"))
      (node (ref "SK5") (pin "1") (pinfunction "1_1") (pintype "unspecified"))
      (node (ref "SK5") (pin "2") (pinfunction "2_2") (pintype "unspecified"))
      (node (ref "SK8") (pin "14") (pinfunction "14_14") (pintype "unspecified"))
      (node (ref "SK9") (pin "14") (pinfunction "14_14") (pintype "unspecified"))
    )
    (net (code "118") (name "unconnected-(SK2-Pad15)") (class "Default")
      (node (ref "SK2") (pin "15") (pinfunction "15_15") (pintype "unspecified"))
    )
    (net (code "119") (name "unconnected-(SK3-Pad6)") (class "Default")
      (node (ref "SK3") (pin "6") (pinfunction "6_6") (pintype "unspecified"))
    )
    (net (code "120") (name "unconnected-(SK3-Pad8)") (class "Default")
      (node (ref "SK3") (pin "8") (pinfunction "8_8") (pintype "unspecified"))
    )
    (net (code "121") (name "unconnected-(SK3-Pad10)") (class "Default")
      (node (ref "SK3") (pin "10") (pinfunction "10_10") (pintype "unspecified"))
    )
    (net (code "122") (name "unconnected-(SK3-Pad12)") (class "Default")
      (node (ref "SK3") (pin "12") (pinfunction "12_12") (pintype "unspecified"))
    )
    (net (code "123") (name "unconnected-(SK4-Pad6)") (class "Default")
      (node (ref "SK4") (pin "6") (pinfunction "6_6") (pintype "unspecified"))
    )
    (net (code "124") (name "unconnected-(SK4-Pad8)") (class "Default")
      (node (ref "SK4") (pin "8") (pinfunction "8_8") (pintype "unspecified"))
    )
    (net (code "125") (name "unconnected-(SK4-Pad10)") (class "Default")
      (node (ref "SK4") (pin "10") (pinfunction "10_10") (pintype "unspecified"))
    )
    (net (code "126") (name "unconnected-(SK4-Pad12)") (class "Default")
      (node (ref "SK4") (pin "12") (pinfunction "12_12") (pintype "unspecified"))
    )
    (net (code "127") (name "unconnected-(SK5-Pad6)") (class "Default")
      (node (ref "SK5") (pin "6") (pinfunction "6_6") (pintype "unspecified"))
    )
    (net (code "128") (name "unconnected-(SK5-Pad8)") (class "Default")
      (node (ref "SK5") (pin "8") (pinfunction "8_8") (pintype "unspecified"))
    )
    (net (code "129") (name "unconnected-(SK5-Pad10)") (class "Default")
      (node (ref "SK5") (pin "10") (pinfunction "10_10") (pintype "unspecified"))
    )
    (net (code "130") (name "unconnected-(SK5-Pad20)") (class "Default")
      (node (ref "SK5") (pin "20") (pinfunction "20_20") (pintype "unspecified"))
    )
    (net (code "131") (name "unconnected-(SK7-Pad6)") (class "Default")
      (node (ref "SK7") (pin "6") (pinfunction "6_6") (pintype "unspecified"))
    )
    (net (code "132") (name "unconnected-(SK7-Pad8)") (class "Default")
      (node (ref "SK7") (pin "8") (pinfunction "8_8") (pintype "unspecified"))
    )
    (net (code "133") (name "unconnected-(SK7-Pad11)") (class "Default")
      (node (ref "SK7") (pin "11") (pinfunction "11_11") (pintype "unspecified"))
    )
    (net (code "134") (name "unconnected-(SK8-Pad1)") (class "Default")
      (node (ref "SK8") (pin "1") (pinfunction "1_1") (pintype "unspecified"))
    )
    (net (code "135") (name "unconnected-(SK8-Pad4)") (class "Default")
      (node (ref "SK8") (pin "4") (pinfunction "4_4") (pintype "unspecified"))
    )
    (net (code "136") (name "unconnected-(SK9-Pad2)") (class "Default")
      (node (ref "SK9") (pin "2") (pinfunction "2_2") (pintype "unspecified"))
    )
    (net (code "137") (name "unconnected-(SK9-Pad4)") (class "Default")
      (node (ref "SK9") (pin "4") (pinfunction "4_4") (pintype "unspecified"))
    )
    (net (code "138") (name "unconnected-(SK9-Pad6)") (class "Default")
      (node (ref "SK9") (pin "6") (pinfunction "6_6") (pintype "unspecified"))
    )
    (net (code "139") (name "unconnected-(SK9-Pad12)") (class "Default")
      (node (ref "SK9") (pin "12") (pinfunction "12_12") (pintype "unspecified"))
    )
    (net (code "140") (name "unconnected-(SK10-Pad1)") (class "Default")
      (node (ref "SK10") (pin "1") (pinfunction "1_1") (pintype "unspecified"))
    )
    (net (code "141") (name "unconnected-(SK10-Pad2)") (class "Default")
      (node (ref "SK10") (pin "2") (pinfunction "2_2") (pintype "unspecified"))
    )
    (net (code "142") (name "unconnected-(SK10-Pad3)") (class "Default")
      (node (ref "SK10") (pin "3") (pinfunction "3_3") (pintype "unspecified"))
    )
    (net (code "143") (name "unconnected-(SK10-Pad4)") (class "Default")
      (node (ref "SK10") (pin "4") (pinfunction "4_4") (pintype "unspecified"))
    )
    (net (code "144") (name "unconnected-(SK10-Pad5)") (class "Default")
      (node (ref "SK10") (pin "5") (pinfunction "5_5") (pintype "unspecified"))
    )
    (net (code "145") (name "unconnected-(SK10-Pad6)") (class "Default")
      (node (ref "SK10") (pin "6") (pinfunction "6_6") (pintype "unspecified"))
    )
    (net (code "146") (name "unconnected-(SK10-Pad12)") (class "Default")
      (node (ref "SK10") (pin "12") (pinfunction "12_12") (pintype "unspecified"))
    )
    (net (code "147") (name "unconnected-(SK10-Pad13)") (class "Default")
      (node (ref "SK10") (pin "13") (pinfunction "13_13") (pintype "unspecified"))
    )
    (net (code "148") (name "unconnected-(SK11-Pad4)") (class "Default")
      (node (ref "SK11") (pin "4") (pinfunction "4_4") (pintype "unspecified"))
    )
    (net (code "149") (name "unconnected-(SK11-Pad6)") (class "Default")
      (node (ref "SK11") (pin "6") (pinfunction "6_6") (pintype "unspecified"))
    )
    (net (code "150") (name "unconnected-(SK11-Pad8)") (class "Default")
      (node (ref "SK11") (pin "8") (pinfunction "8_8") (pintype "unspecified"))
    )
    (net (code "151") (name "unconnected-(SK11-Pad10)") (class "Default")
      (node (ref "SK11") (pin "10") (pinfunction "10_10") (pintype "unspecified"))
    )
    (net (code "152") (name "unconnected-(SK12-Pad2)") (class "Default")
      (node (ref "SK12") (pin "2") (pinfunction "2_2") (pintype "unspecified"))
    )
    (net (code "153") (name "unconnected-(SK12-Pad4)") (class "Default")
      (node (ref "SK12") (pin "4") (pinfunction "4_4") (pintype "unspecified"))
    )
    (net (code "154") (name "unconnected-(SK12-Pad6)") (class "Default")
      (node (ref "SK12") (pin "6") (pinfunction "6_6") (pintype "unspecified"))
    )
    (net (code "155") (name "unconnected-(SK12-Pad12)") (class "Default")
      (node (ref "SK12") (pin "12") (pinfunction "12_12") (pintype "unspecified"))
    )
    (net (code "156") (name "unconnected-(SK12-Pad13)") (class "Default")
      (node (ref "SK12") (pin "13") (pinfunction "13_13") (pintype "unspecified"))
    )
    (net (code "157") (name "unconnected-(SK13-Pad2)") (class "Default")
      (node (ref "SK13") (pin "2") (pinfunction "2_2") (pintype "unspecified"))
    )
    (net (code "158") (name "unconnected-(SK13-Pad4)") (class "Default")
      (node (ref "SK13") (pin "4") (pinfunction "4_4") (pintype "unspecified"))
    )
    (net (code "159") (name "unconnected-(SK13-Pad6)") (class "Default")
      (node (ref "SK13") (pin "6") (pinfunction "6_6") (pintype "unspecified"))
    )
    (net (code "160") (name "unconnected-(SK13-Pad12)") (class "Default")
      (node (ref "SK13") (pin "12") (pinfunction "12_12") (pintype "unspecified"))
    )
    (net (code "161") (name "unconnected-(SK14-Pad2)") (class "Default")
      (node (ref "SK14") (pin "2") (pinfunction "2_2") (pintype "unspecified"))
    )
    (net (code "162") (name "unconnected-(SK14-Pad4)") (class "Default")
      (node (ref "SK14") (pin "4") (pinfunction "4_4") (pintype "unspecified"))
    )
    (net (code "163") (name "unconnected-(SK14-Pad6)") (class "Default")
      (node (ref "SK14") (pin "6") (pinfunction "6_6") (pintype "unspecified"))
    )
    (net (code "164") (name "unconnected-(SK14-Pad12)") (class "Default")
      (node (ref "SK14") (pin "12") (pinfunction "12_12") (pintype "unspecified"))
    )
    (net (code "165") (name "unconnected-(SK14-Pad14)") (class "Default")
      (node (ref "SK14") (pin "14") (pinfunction "14_14") (pintype "unspecified"))
    )
    (net (code "166") (name "unconnected-(SK16-Pad3)") (class "Default")
      (node (ref "SK16") (pin "3") (pinfunction "3_3") (pintype "unspecified"))
    )
    (net (code "167") (name "unconnected-(SK16-Pad6)") (class "Default")
      (node (ref "SK16") (pin "6") (pinfunction "6_6") (pintype "unspecified"))
    )
    (net (code "168") (name "unconnected-(SK16-Pad8)") (class "Default")
      (node (ref "SK16") (pin "8") (pinfunction "8_8") (pintype "unspecified"))
    )
    (net (code "169") (name "unconnected-(SK22-Pad3)") (class "Default")
      (node (ref "SK22") (pin "3") (pinfunction "3_3") (pintype "unspecified"))
    )
    (net (code "170") (name "unconnected-(SK22-Pad4)") (class "Default")
      (node (ref "SK22") (pin "4") (pinfunction "4_4") (pintype "unspecified"))
    )
    (net (code "171") (name "unconnected-(SK22-Pad5)") (class "Default")
      (node (ref "SK22") (pin "5") (pinfunction "5_5") (pintype "unspecified"))
    )
    (net (code "172") (name "unconnected-(SK22-Pad6)") (class "Default")
      (node (ref "SK22") (pin "6") (pinfunction "6_6") (pintype "unspecified"))
    )
    (net (code "173") (name "unconnected-(SK22-Pad15)") (class "Default")
      (node (ref "SK22") (pin "15") (pinfunction "15_15") (pintype "unspecified"))
    )
    (net (code "174") (name "unconnected-(SK23-Pad5)") (class "Default")
      (node (ref "SK23") (pin "5") (pinfunction "5_5") (pintype "unspecified"))
    )
    (net (code "175") (name "unconnected-(SK23-Pad6)") (class "Default")
      (node (ref "SK23") (pin "6") (pinfunction "6_6") (pintype "unspecified"))
    )
    (net (code "176") (name "unconnected-(SK23-Pad15)") (class "Default")
      (node (ref "SK23") (pin "15") (pinfunction "15_15") (pintype "unspecified"))
    )
    (net (code "177") (name "unconnected-(SK26-Pad6)") (class "Default")
      (node (ref "SK26") (pin "6") (pinfunction "6_6") (pintype "unspecified"))
    )
    (net (code "178") (name "unconnected-(SK26-Pad8)") (class "Default")
      (node (ref "SK26") (pin "8") (pinfunction "8_8") (pintype "unspecified"))
    )
    (net (code "179") (name "unconnected-(SK26-Pad10)") (class "Default")
      (node (ref "SK26") (pin "10") (pinfunction "10_10") (pintype "unspecified"))
    )
    (net (code "180") (name "unconnected-(SK26-Pad12)") (class "Default")
      (node (ref "SK26") (pin "12") (pinfunction "12_12") (pintype "unspecified"))
    )
    (net (code "181") (name "unconnected-(SK26-Pad19)") (class "Default")
      (node (ref "SK26") (pin "19") (pinfunction "19_19") (pintype "unspecified"))
    )
    (net (code "182") (name "unconnected-(SK27-Pad15)") (class "Default")
      (node (ref "SK27") (pin "15") (pinfunction "15_15") (pintype "unspecified"))
    )
    (net (code "183") (name "unconnected-(SK28-Pad9)") (class "Default")
      (node (ref "SK28") (pin "9") (pinfunction "9_9") (pintype "unspecified"))
    )
    (net (code "184") (name "unconnected-(SK31-Pad2)") (class "Default")
      (node (ref "SK31") (pin "2") (pinfunction "2_2") (pintype "unspecified"))
    )
    (net (code "185") (name "unconnected-(SK32-Pad2)") (class "Default")
      (node (ref "SK32") (pin "2") (pinfunction "2_2") (pintype "unspecified"))
    )
    (net (code "186") (name "unconnected-(SK33-Pad2)") (class "Default")
      (node (ref "SK33") (pin "2") (pinfunction "2_2") (pintype "unspecified"))
    )
    (net (code "187") (name "unconnected-(SK33-Pad4)") (class "Default")
      (node (ref "SK33") (pin "4") (pinfunction "4_4") (pintype "unspecified"))
    )
    (net (code "188") (name "unconnected-(SK33-Pad6)") (class "Default")
      (node (ref "SK33") (pin "6") (pinfunction "6_6") (pintype "unspecified"))
    )
    (net (code "189") (name "unconnected-(SK33-Pad10)") (class "Default")
      (node (ref "SK33") (pin "10") (pinfunction "10_10") (pintype "unspecified"))
    )
    (net (code "190") (name "unconnected-(SK33-Pad12)") (class "Default")
      (node (ref "SK33") (pin "12") (pinfunction "12_12") (pintype "unspecified"))
    )
    (net (code "191") (name "unconnected-(SK37-Pad14)") (class "Default")
      (node (ref "SK37") (pin "14") (pinfunction "14_14") (pintype "unspecified"))
    )
    (net (code "192") (name "unconnected-(SK37-Pad16)") (class "Default")
      (node (ref "SK37") (pin "16") (pinfunction "16_16") (pintype "unspecified"))
    )
    (net (code "193") (name "unconnected-(SK37-Pad18)") (class "Default")
      (node (ref "SK37") (pin "18") (pinfunction "18_18") (pintype "unspecified"))
    )
    (net (code "194") (name "unconnected-(SK37-Pad20)") (class "Default")
      (node (ref "SK37") (pin "20") (pinfunction "20_20") (pintype "unspecified"))
    )
    (net (code "195") (name "unconnected-(SW1-Pad1)") (class "Default")
      (node (ref "SW1") (pin "1") (pinfunction "1_1") (pintype "unspecified"))
    )
    (net (code "196") (name "unconnected-(SW1-Pad2)") (class "Default")
      (node (ref "SW1") (pin "2") (pinfunction "2_2") (pintype "unspecified"))
    )
    (net (code "197") (name "unconnected-(SW1-Pad3)") (class "Default")
      (node (ref "SW1") (pin "3") (pinfunction "3_3") (pintype "unspecified"))
    )
    (net (code "198") (name "unconnected-(SW1-Pad4)") (class "Default")
      (node (ref "SW1") (pin "4") (pinfunction "4_4") (pintype "unspecified"))
    )
    (net (code "199") (name "unconnected-(SW1-Pad5)") (class "Default")
      (node (ref "SW1") (pin "5") (pinfunction "5_5") (pintype "unspecified"))
    )
    (net (code "200") (name "unconnected-(SW1-Pad6)") (class "Default")
      (node (ref "SW1") (pin "6") (pinfunction "6_6") (pintype "unspecified"))
    )
    (net (code "201") (name "unconnected-(SW1-Pad7)") (class "Default")
      (node (ref "SW1") (pin "7") (pinfunction "7_7") (pintype "unspecified"))
    )
    (net (code "202") (name "unconnected-(SW1-Pad8)") (class "Default")
      (node (ref "SW1") (pin "8") (pinfunction "8_8") (pintype "unspecified"))
    )
    (net (code "203") (name "unconnected-(SW1-Pad9)") (class "Default")
      (node (ref "SW1") (pin "9") (pinfunction "9_9") (pintype "unspecified"))
    )
    (net (code "204") (name "unconnected-(SW1-Pad10)") (class "Default")
      (node (ref "SW1") (pin "10") (pinfunction "10_10") (pintype "unspecified"))
    )
    (net (code "205") (name "unconnected-(SW1-Pad11)") (class "Default")
      (node (ref "SW1") (pin "11") (pinfunction "11_11") (pintype "unspecified"))
    )
    (net (code "206") (name "unconnected-(SW1-Pad12)") (class "Default")
      (node (ref "SW1") (pin "12") (pinfunction "12_12") (pintype "unspecified"))
    )
    (net (code "207") (name "unconnected-(SW1-Pad13)") (class "Default")
      (node (ref "SW1") (pin "13") (pinfunction "13_13") (pintype "unspecified"))
    )
    (net (code "208") (name "unconnected-(SW1-Pad14)") (class "Default")
      (node (ref "SW1") (pin "14") (pinfunction "14_14") (pintype "unspecified"))
    )
    (net (code "209") (name "unconnected-(SW1-Pad15)") (class "Default")
      (node (ref "SW1") (pin "15") (pinfunction "15_15") (pintype "unspecified"))
    )
    (net (code "210") (name "unconnected-(SW1-Pad16)") (class "Default")
      (node (ref "SW1") (pin "16") (pinfunction "16_16") (pintype "unspecified"))
    )
    (net (code "211") (name "unconnected-(SW2-Pad1)") (class "Default")
      (node (ref "SW2") (pin "1") (pinfunction "1_1") (pintype "unspecified"))
    )
    (net (code "212") (name "unconnected-(SW2-Pad2)") (class "Default")
      (node (ref "SW2") (pin "2") (pinfunction "2_2") (pintype "unspecified"))
    )
    (net (code "213") (name "unconnected-(SW2-Pad3)") (class "Default")
      (node (ref "SW2") (pin "3") (pinfunction "3_3") (pintype "unspecified"))
    )
    (net (code "214") (name "unconnected-(SW2-Pad4)") (class "Default")
      (node (ref "SW2") (pin "4") (pinfunction "4_4") (pintype "unspecified"))
    )
    (net (code "215") (name "unconnected-(SW2-Pad5)") (class "Default")
      (node (ref "SW2") (pin "5") (pinfunction "5_5") (pintype "unspecified"))
    )
    (net (code "216") (name "unconnected-(SW2-Pad6)") (class "Default")
      (node (ref "SW2") (pin "6") (pinfunction "6_6") (pintype "unspecified"))
    )
    (net (code "217") (name "unconnected-(SW2-Pad7)") (class "Default")
      (node (ref "SW2") (pin "7") (pinfunction "7_7") (pintype "unspecified"))
    )
    (net (code "218") (name "unconnected-(SW2-Pad8)") (class "Default")
      (node (ref "SW2") (pin "8") (pinfunction "8_8") (pintype "unspecified"))
    )
    (net (code "219") (name "unconnected-(SW2-Pad9)") (class "Default")
      (node (ref "SW2") (pin "9") (pinfunction "9_9") (pintype "unspecified"))
    )
    (net (code "220") (name "unconnected-(SW2-Pad10)") (class "Default")
      (node (ref "SW2") (pin "10") (pinfunction "10_10") (pintype "unspecified"))
    )
    (net (code "221") (name "unconnected-(SW2-Pad11)") (class "Default")
      (node (ref "SW2") (pin "11") (pinfunction "11_11") (pintype "unspecified"))
    )
    (net (code "222") (name "unconnected-(SW2-Pad12)") (class "Default")
      (node (ref "SW2") (pin "12") (pinfunction "12_12") (pintype "unspecified"))
    )
    (net (code "223") (name "unconnected-(SW2-Pad13)") (class "Default")
      (node (ref "SW2") (pin "13") (pinfunction "13_13") (pintype "unspecified"))
    )
    (net (code "224") (name "unconnected-(SW2-Pad14)") (class "Default")
      (node (ref "SW2") (pin "14") (pinfunction "14_14") (pintype "unspecified"))
    )
    (net (code "225") (name "unconnected-(SW2-Pad15)") (class "Default")
      (node (ref "SW2") (pin "15") (pinfunction "15_15") (pintype "unspecified"))
    )
    (net (code "226") (name "unconnected-(SW2-Pad16)") (class "Default")
      (node (ref "SW2") (pin "16") (pinfunction "16_16") (pintype "unspecified"))
    )
    (net (code "227") (name "unconnected-(SW3-Pad5)") (class "Default")
      (node (ref "SW3") (pin "5") (pinfunction "5_5") (pintype "unspecified"))
    )
    (net (code "228") (name "unconnected-(SW3-Pad6)") (class "Default")
      (node (ref "SW3") (pin "6") (pinfunction "6_6") (pintype "unspecified"))
    )
    (net (code "229") (name "unconnected-(SW3-Pad7)") (class "Default")
      (node (ref "SW3") (pin "7") (pinfunction "7_7") (pintype "unspecified"))
    )
    (net (code "230") (name "unconnected-(SW3-Pad8)") (class "Default")
      (node (ref "SW3") (pin "8") (pinfunction "8_8") (pintype "unspecified"))
    )
    (net (code "231") (name "unconnected-(SW4-Pad1)") (class "Default")
      (node (ref "SW4") (pin "1") (pinfunction "1_1") (pintype "unspecified"))
    )
    (net (code "232") (name "unconnected-(SW4-Pad2)") (class "Default")
      (node (ref "SW4") (pin "2") (pinfunction "2_2") (pintype "unspecified"))
    )
    (net (code "233") (name "unconnected-(SW4-Pad3)") (class "Default")
      (node (ref "SW4") (pin "3") (pinfunction "3_3") (pintype "unspecified"))
    )
    (net (code "234") (name "unconnected-(SW4-Pad4)") (class "Default")
      (node (ref "SW4") (pin "4") (pinfunction "4_4") (pintype "unspecified"))
    )
    (net (code "235") (name "unconnected-(SW4-Pad5)") (class "Default")
      (node (ref "SW4") (pin "5") (pinfunction "5_5") (pintype "unspecified"))
    )
    (net (code "236") (name "unconnected-(SW4-Pad6)") (class "Default")
      (node (ref "SW4") (pin "6") (pinfunction "6_6") (pintype "unspecified"))
    )
    (net (code "237") (name "unconnected-(SW4-Pad7)") (class "Default")
      (node (ref "SW4") (pin "7") (pinfunction "7_7") (pintype "unspecified"))
    )
    (net (code "238") (name "unconnected-(SW4-Pad8)") (class "Default")
      (node (ref "SW4") (pin "8") (pinfunction "8_8") (pintype "unspecified"))
    )
    (net (code "239") (name "unconnected-(U2-Pad1)") (class "Default")
      (node (ref "U2") (pin "1") (pinfunction "1_1") (pintype "unspecified"))
    )
    (net (code "240") (name "unconnected-(U2-Pad2)") (class "Default")
      (node (ref "U2") (pin "2") (pinfunction "2_2") (pintype "unspecified"))
    )
    (net (code "241") (name "unconnected-(U2-Pad3)") (class "Default")
      (node (ref "U2") (pin "3") (pinfunction "3_3") (pintype "unspecified"))
    )
    (net (code "242") (name "unconnected-(U2-Pad4)") (class "Default")
      (node (ref "U2") (pin "4") (pinfunction "4_4") (pintype "unspecified"))
    )
    (net (code "243") (name "unconnected-(U2-Pad5)") (class "Default")
      (node (ref "U2") (pin "5") (pinfunction "5_5") (pintype "unspecified"))
    )
    (net (code "244") (name "unconnected-(U2-Pad6)") (class "Default")
      (node (ref "U2") (pin "6") (pinfunction "6_6") (pintype "unspecified"))
    )
    (net (code "245") (name "unconnected-(U2-Pad7)") (class "Default")
      (node (ref "U2") (pin "7") (pinfunction "7_7") (pintype "unspecified"))
    )
    (net (code "246") (name "unconnected-(U2-Pad10)") (class "Default")
      (node (ref "U2") (pin "10") (pinfunction "10_10") (pintype "unspecified"))
    )
    (net (code "247") (name "unconnected-(U2-Pad20)") (class "Default")
      (node (ref "U2") (pin "20") (pinfunction "20_20") (pintype "unspecified"))
    )
    (net (code "248") (name "unconnected-(U2-Pad26)") (class "Default")
      (node (ref "U2") (pin "26") (pinfunction "26_26") (pintype "unspecified"))
    )
    (net (code "249") (name "unconnected-(U4-Pad1)") (class "Default")
      (node (ref "U4") (pin "1") (pinfunction "1_1") (pintype "unspecified"))
    )
    (net (code "250") (name "unconnected-(U4-Pad2)") (class "Default")
      (node (ref "U4") (pin "2") (pinfunction "2_2") (pintype "unspecified"))
    )
    (net (code "251") (name "unconnected-(U4-Pad3)") (class "Default")
      (node (ref "U4") (pin "3") (pinfunction "3_3") (pintype "unspecified"))
    )
    (net (code "252") (name "unconnected-(U4-Pad4)") (class "Default")
      (node (ref "U4") (pin "4") (pinfunction "4_4") (pintype "unspecified"))
    )
    (net (code "253") (name "unconnected-(U4-Pad5)") (class "Default")
      (node (ref "U4") (pin "5") (pinfunction "5_5") (pintype "unspecified"))
    )
    (net (code "254") (name "unconnected-(U4-Pad6)") (class "Default")
      (node (ref "U4") (pin "6") (pinfunction "6_6") (pintype "unspecified"))
    )
    (net (code "255") (name "unconnected-(U4-Pad7)") (class "Default")
      (node (ref "U4") (pin "7") (pinfunction "7_7") (pintype "unspecified"))
    )
    (net (code "256") (name "unconnected-(U4-Pad8)") (class "Default")
      (node (ref "U4") (pin "8") (pinfunction "8_8") (pintype "unspecified"))
    )
    (net (code "257") (name "unconnected-(U4-Pad9)") (class "Default")
      (node (ref "U4") (pin "9") (pinfunction "9_9") (pintype "unspecified"))
    )
    (net (code "258") (name "unconnected-(U4-Pad10)") (class "Default")
      (node (ref "U4") (pin "10") (pinfunction "10_10") (pintype "unspecified"))
    )
    (net (code "259") (name "unconnected-(U4-Pad20)") (class "Default")
      (node (ref "U4") (pin "20") (pinfunction "20_20") (pintype "unspecified"))
    )
    (net (code "260") (name "unconnected-(U4-Pad26)") (class "Default")
      (node (ref "U4") (pin "26") (pinfunction "26_26") (pintype "unspecified"))
    )
    (net (code "261") (name "unconnected-(U5-Pad9)") (class "Default")
      (node (ref "U5") (pin "9") (pinfunction "9_9") (pintype "unspecified"))
    )
    (net (code "262") (name "unconnected-(U6-Pad15)") (class "Default")
      (node (ref "U6") (pin "15") (pinfunction "15_15") (pintype "unspecified"))
    )
    (net (code "263") (name "unconnected-(U7-Pad1)") (class "Default")
      (node (ref "U7") (pin "1") (pinfunction "1_1") (pintype "unspecified"))
    )
    (net (code "264") (name "unconnected-(U7-Pad2)") (class "Default")
      (node (ref "U7") (pin "2") (pinfunction "2_2") (pintype "unspecified"))
    )
    (net (code "265") (name "unconnected-(U7-Pad7)") (class "Default")
      (node (ref "U7") (pin "7") (pinfunction "7_7") (pintype "unspecified"))
    )
    (net (code "266") (name "unconnected-(U7-Pad15)") (class "Default")
      (node (ref "U7") (pin "15") (pinfunction "15_15") (pintype "unspecified"))
    )
    (net (code "267") (name "unconnected-(U10-Pad1)") (class "Default")
      (node (ref "U10") (pin "1") (pinfunction "1_1") (pintype "unspecified"))
    )
    (net (code "268") (name "unconnected-(U10-Pad2)") (class "Default")
      (node (ref "U10") (pin "2") (pinfunction "2_2") (pintype "unspecified"))
    )
    (net (code "269") (name "unconnected-(U10-Pad15)") (class "Default")
      (node (ref "U10") (pin "15") (pinfunction "15_15") (pintype "unspecified"))
    )
    (net (code "270") (name "unconnected-(U11-Pad1)") (class "Default")
      (node (ref "U11") (pin "1") (pinfunction "1_1") (pintype "unspecified"))
    )
    (net (code "271") (name "unconnected-(U11-Pad2)") (class "Default")
      (node (ref "U11") (pin "2") (pinfunction "2_2") (pintype "unspecified"))
    )
    (net (code "272") (name "unconnected-(U11-Pad3)") (class "Default")
      (node (ref "U11") (pin "3") (pinfunction "3_3") (pintype "unspecified"))
    )
    (net (code "273") (name "unconnected-(U11-Pad4)") (class "Default")
      (node (ref "U11") (pin "4") (pinfunction "4_4") (pintype "unspecified"))
    )
    (net (code "274") (name "unconnected-(U11-Pad5)") (class "Default")
      (node (ref "U11") (pin "5") (pinfunction "5_5") (pintype "unspecified"))
    )
    (net (code "275") (name "unconnected-(U11-Pad6)") (class "Default")
      (node (ref "U11") (pin "6") (pinfunction "6_6") (pintype "unspecified"))
    )
    (net (code "276") (name "unconnected-(U11-Pad7)") (class "Default")
      (node (ref "U11") (pin "7") (pinfunction "7_7") (pintype "unspecified"))
    )
    (net (code "277") (name "unconnected-(U11-Pad10)") (class "Default")
      (node (ref "U11") (pin "10") (pinfunction "10_10") (pintype "unspecified"))
    )
    (net (code "278") (name "unconnected-(U11-Pad20)") (class "Default")
      (node (ref "U11") (pin "20") (pinfunction "20_20") (pintype "unspecified"))
    )
    (net (code "279") (name "unconnected-(U11-Pad26)") (class "Default")
      (node (ref "U11") (pin "26") (pinfunction "26_26") (pintype "unspecified"))
    )
  )
)
